# clock10.net
KiCad netlist of a schematic drawn in EAGLE
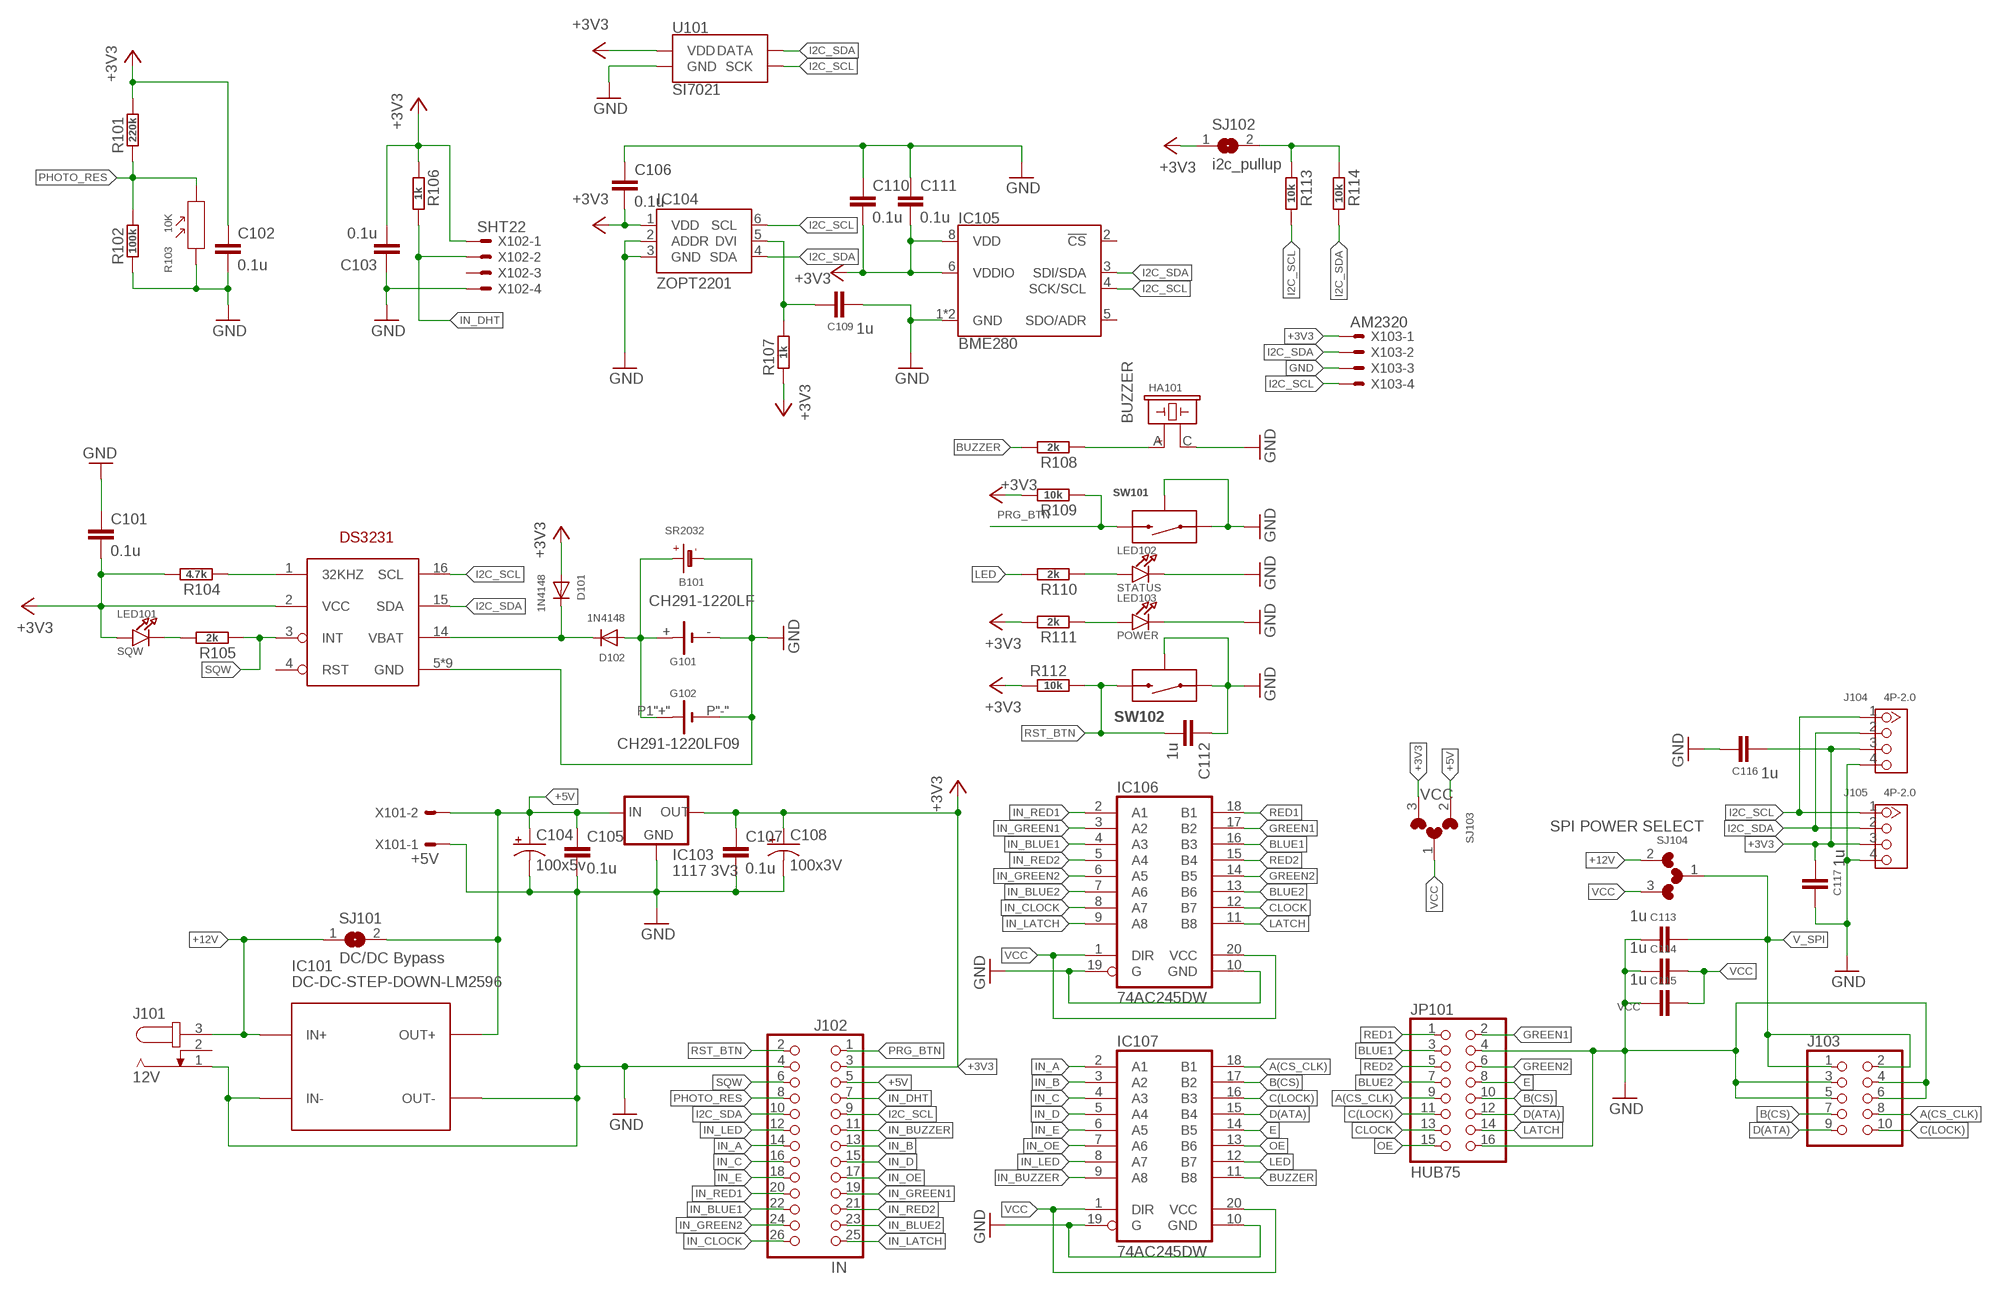
[diagram p0: schematic, sheet 1]
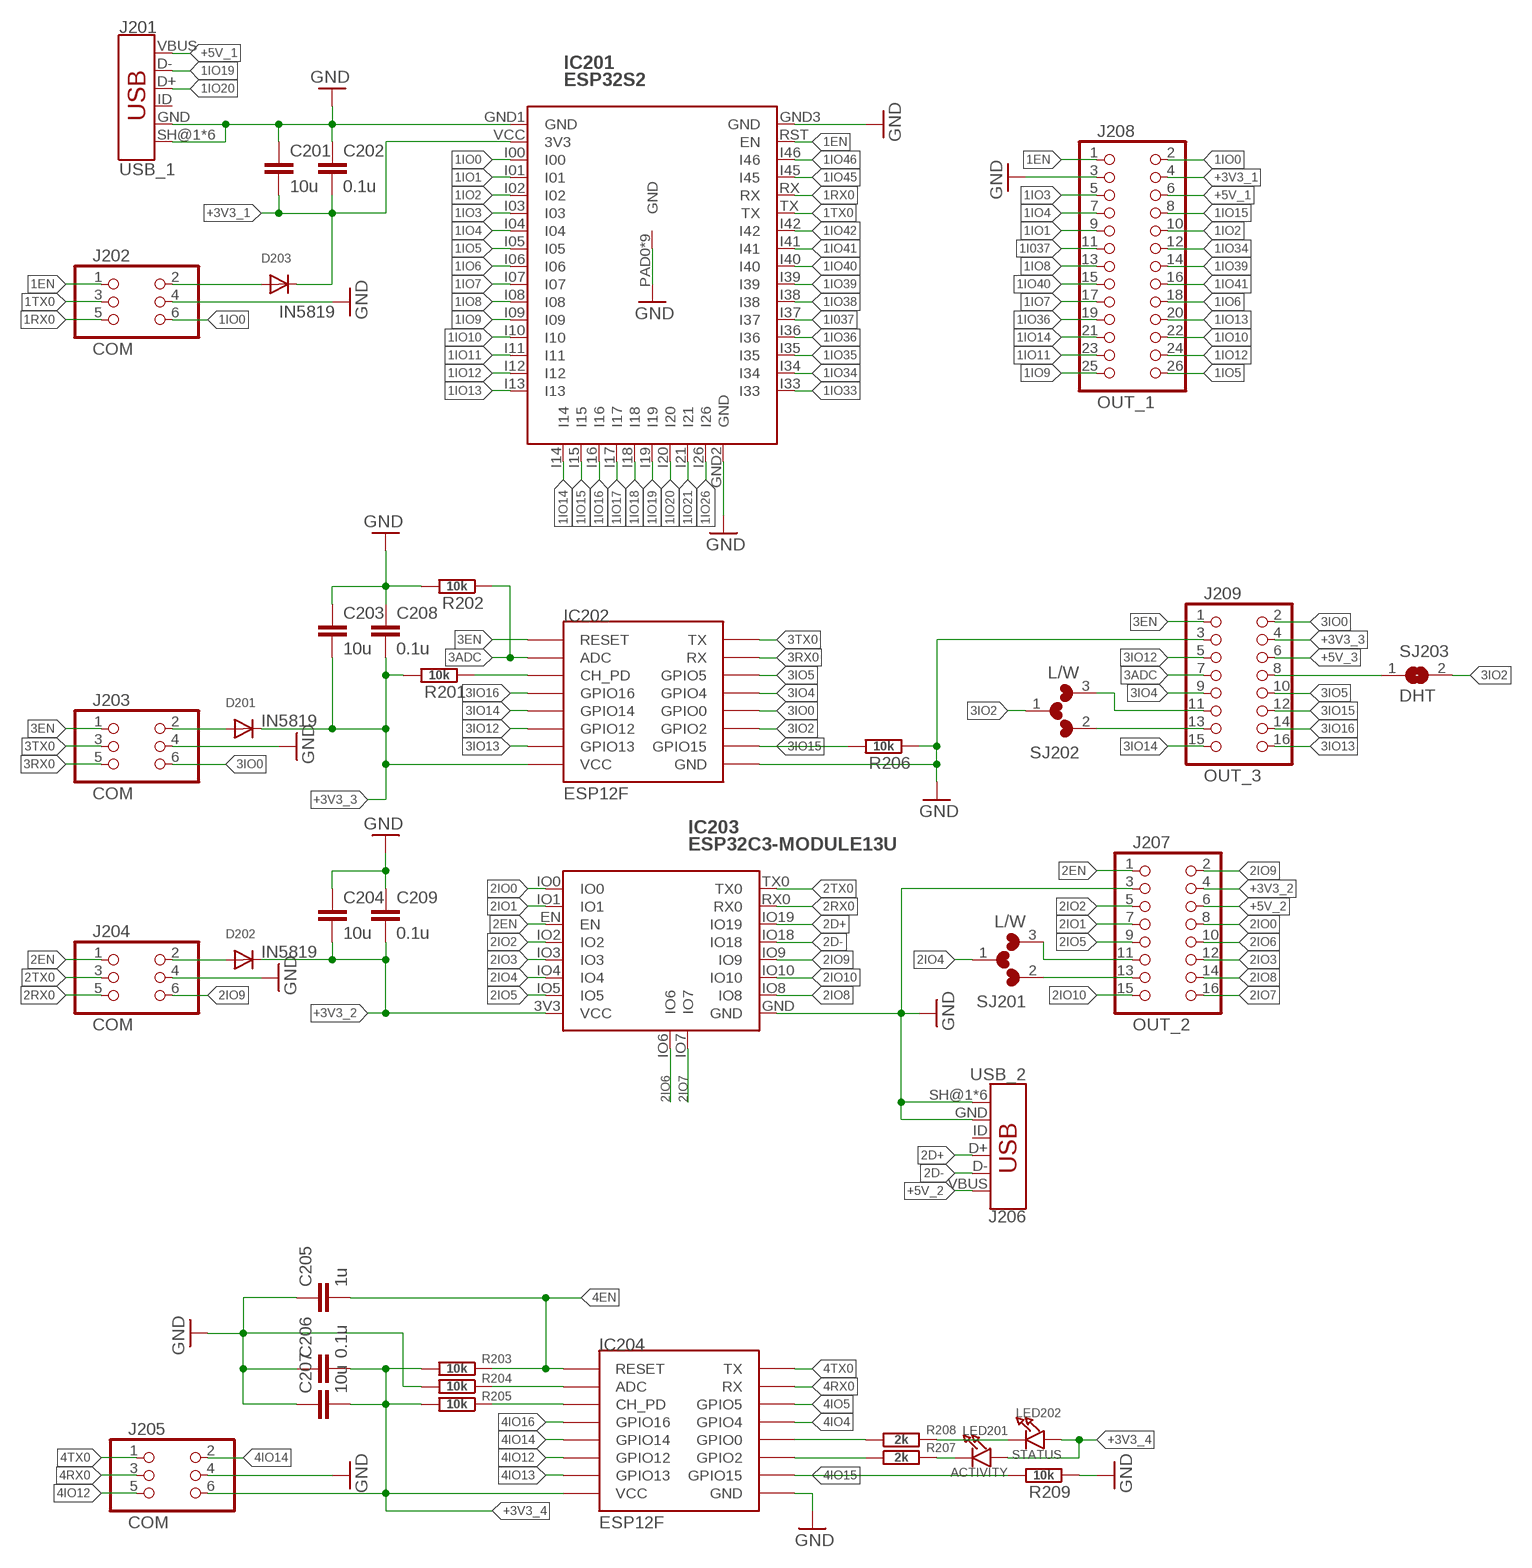
[diagram p1: schematic, sheet 2]
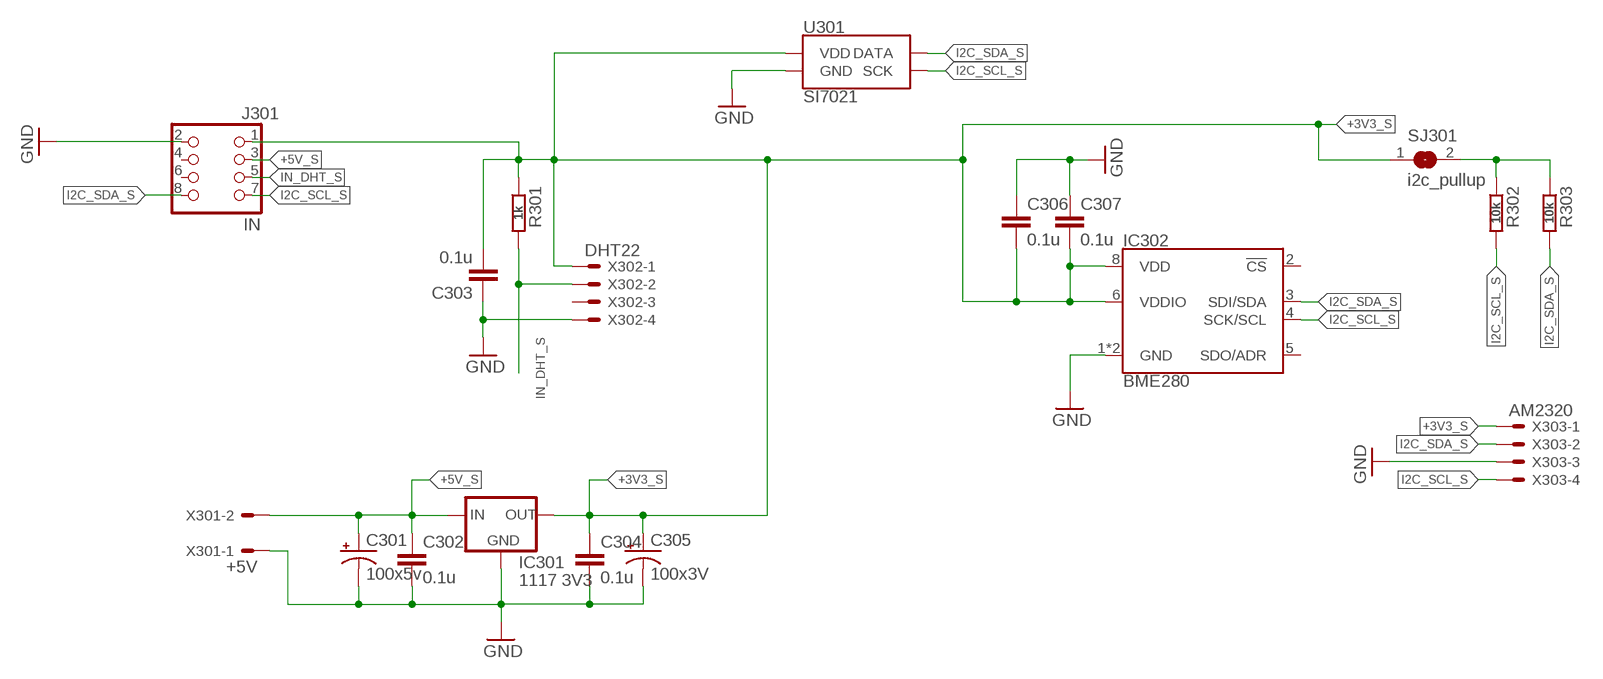
[diagram p2: schematic, sheet 3]

(export (version "E")
  (design (tool "Eeschema 10.0.6"))
  (components
    (comp (ref "C201")
      (value "10u")
      (footprint "eagle-import:0603-CAP")
      (libsource (lib "eagle-import") (part "CAP0603-CAP"))
    )
    (comp (ref "C202")
      (value "0.1u")
      (footprint "eagle-import:0603-CAP")
      (libsource (lib "eagle-import") (part "CAP0603-CAP"))
    )
    (comp (ref "C203")
      (value "10u")
      (footprint "eagle-import:0603-CAP")
      (libsource (lib "eagle-import") (part "CAP0603-CAP"))
    )
    (comp (ref "C204")
      (value "10u")
      (footprint "eagle-import:0603-CAP")
      (libsource (lib "eagle-import") (part "CAP0603-CAP"))
    )
    (comp (ref "C205")
      (value "1u")
      (footprint "eagle-import:0603-CAP")
      (libsource (lib "eagle-import") (part "CAP0603-CAP"))
    )
    (comp (ref "C206")
      (value "0.1u")
      (footprint "eagle-import:0603-CAP")
      (libsource (lib "eagle-import") (part "CAP0603-CAP"))
    )
    (comp (ref "C207")
      (value "10u")
      (footprint "eagle-import:0603-CAP")
      (libsource (lib "eagle-import") (part "CAP0603-CAP"))
    )
    (comp (ref "C208")
      (value "0.1u")
      (footprint "eagle-import:0603-CAP")
      (libsource (lib "eagle-import") (part "CAP0603-CAP"))
    )
    (comp (ref "C209")
      (value "0.1u")
      (footprint "eagle-import:0603-CAP")
      (libsource (lib "eagle-import") (part "CAP0603-CAP"))
    )
    (comp (ref "D201")
      (value "IN5819")
      (footprint "eagle-import:SOD123")
      (libsource (lib "eagle-import") (part "DIODE-SOD123"))
    )
    (comp (ref "D202")
      (value "IN5819")
      (footprint "eagle-import:SOD123")
      (libsource (lib "eagle-import") (part "DIODE-SOD123"))
    )
    (comp (ref "D203")
      (value "IN5819")
      (footprint "eagle-import:SOD123")
      (libsource (lib "eagle-import") (part "DIODE-SOD123"))
    )
    (comp (ref "IC201")
      (value "ESP32S2")
      (footprint "eagle-import:ESP-12K")
      (libsource (lib "eagle-import") (part "ESP32S2-MODULEAI"))
    )
    (comp (ref "IC202")
      (value "ESP12F")
      (footprint "eagle-import:ESP12-SMD")
      (libsource (lib "eagle-import") (part "ESP12SMD"))
    )
    (comp (ref "IC203")
      (value "ESP32C3-MODULE13U")
      (footprint "eagle-import:ESP32C3-13U")
      (libsource (lib "eagle-import") (part "ESP32C3-MODULE13U"))
    )
    (comp (ref "IC204")
      (value "ESP12F")
      (footprint "eagle-import:ESP12-SMD")
      (libsource (lib "eagle-import") (part "ESP12SMD"))
    )
    (comp (ref "J201")
      (value "USB_1")
      (footprint "eagle-import:USB-B-MICRO-SMD_MY")
      (libsource (lib "eagle-import") (part "USB_MICRO-BFEMALE_SMT_"))
    )
    (comp (ref "J202")
      (value "COM")
      (footprint "eagle-import:2X03_SMT")
      (libsource (lib "eagle-import") (part "HEADER-2X3SMT"))
    )
    (comp (ref "J203")
      (value "COM")
      (footprint "eagle-import:2X03_SMT")
      (libsource (lib "eagle-import") (part "HEADER-2X3SMT"))
    )
    (comp (ref "J204")
      (value "COM")
      (footprint "eagle-import:2X03_SMT")
      (libsource (lib "eagle-import") (part "HEADER-2X3SMT"))
    )
    (comp (ref "J205")
      (value "COM")
      (footprint "eagle-import:2X03_SMT")
      (libsource (lib "eagle-import") (part "HEADER-2X3SMT"))
    )
    (comp (ref "J206")
      (value "USB_2")
      (footprint "eagle-import:USB-B-MICRO-SMD_MY")
      (libsource (lib "eagle-import") (part "USB_MICRO-BFEMALE_SMT_"))
    )
    (comp (ref "J207")
      (value "OUT_2")
      (footprint "eagle-import:2X8")
      (libsource (lib "eagle-import") (part "HEADER-2X8"))
    )
    (comp (ref "J208")
      (value "OUT_1")
      (footprint "eagle-import:2X13")
      (libsource (lib "eagle-import") (part "HEADER-2X13"))
    )
    (comp (ref "J209")
      (value "OUT_3")
      (footprint "eagle-import:2X8")
      (libsource (lib "eagle-import") (part "HEADER-2X8"))
    )
    (comp (ref "LED201")
      (value "ACTIVITY")
      (footprint "eagle-import:CHIPLED_0603")
      (libsource (lib "eagle-import") (part "LED0603"))
    )
    (comp (ref "LED202")
      (value "STATUS")
      (footprint "eagle-import:CHIPLED_0603")
      (libsource (lib "eagle-import") (part "LED0603"))
    )
    (comp (ref "R201")
      (value "10k")
      (footprint "eagle-import:R0603")
      (libsource (lib "eagle-import") (part "R-EU_R0603"))
    )
    (comp (ref "R202")
      (value "10k")
      (footprint "eagle-import:R0603")
      (libsource (lib "eagle-import") (part "R-EU_R0603"))
    )
    (comp (ref "R203")
      (value "10k")
      (footprint "eagle-import:R0603")
      (libsource (lib "eagle-import") (part "R-EU_R0603"))
    )
    (comp (ref "R204")
      (value "10k")
      (footprint "eagle-import:R0603")
      (libsource (lib "eagle-import") (part "R-EU_R0603"))
    )
    (comp (ref "R205")
      (value "10k")
      (footprint "eagle-import:R0603")
      (libsource (lib "eagle-import") (part "R-EU_R0603"))
    )
    (comp (ref "R206")
      (value "10k")
      (footprint "eagle-import:R0603")
      (libsource (lib "eagle-import") (part "R-EU_R0603"))
    )
    (comp (ref "R207")
      (value "2k")
      (footprint "eagle-import:R0603")
      (libsource (lib "eagle-import") (part "R-EU_R0603"))
    )
    (comp (ref "R208")
      (value "2k")
      (footprint "eagle-import:R0603")
      (libsource (lib "eagle-import") (part "R-EU_R0603"))
    )
    (comp (ref "R209")
      (value "10k")
      (footprint "eagle-import:R0603")
      (libsource (lib "eagle-import") (part "R-EU_R0603"))
    )
    (comp (ref "SJ201")
      (value "L/W")
      (footprint "eagle-import:MICROBUILDER_SOLDERJUMPER_ARROW_NOPASTE_3")
      (libsource (lib "eagle-import") (part "MICROBUILDER_SOLDERJUMPER3"))
    )
    (comp (ref "SJ202")
      (value "L/W")
      (footprint "eagle-import:MICROBUILDER_SOLDERJUMPER_ARROW_NOPASTE_3")
      (libsource (lib "eagle-import") (part "MICROBUILDER_SOLDERJUMPER3"))
    )
    (comp (ref "SJ203")
      (value "DHT")
      (footprint "eagle-import:MICROBUILDER_SOLDERJUMPER_ARROW_NOPASTE")
      (libsource (lib "eagle-import") (part "MICROBUILDER_SOLDERJUMPER"))
    )
    (comp (ref "C301")
      (value "100x5v")
      (footprint "eagle-import:CPOL-RADIAL-100UF-25V")
      (libsource (lib "eagle-import") (part "CAP_POLPTH1"))
    )
    (comp (ref "C302")
      (value "0.1u")
      (footprint "eagle-import:0603-CAP")
      (libsource (lib "eagle-import") (part "CAP0603-CAP"))
    )
    (comp (ref "C303")
      (value "0.1u")
      (footprint "eagle-import:0603-CAP")
      (libsource (lib "eagle-import") (part "CAP0603-CAP"))
    )
    (comp (ref "C304")
      (value "0.1u")
      (footprint "eagle-import:0603-CAP")
      (libsource (lib "eagle-import") (part "CAP0603-CAP"))
    )
    (comp (ref "C305")
      (value "100x3V")
      (footprint "eagle-import:CPOL-RADIAL-100UF-25V")
      (libsource (lib "eagle-import") (part "CAP_POLPTH1"))
    )
    (comp (ref "C306")
      (value "0.1u")
      (footprint "eagle-import:0603-CAP")
      (libsource (lib "eagle-import") (part "CAP0603-CAP"))
    )
    (comp (ref "C307")
      (value "0.1u")
      (footprint "eagle-import:0603-CAP")
      (libsource (lib "eagle-import") (part "CAP0603-CAP"))
    )
    (comp (ref "IC301")
      (value "1117 3V3")
      (footprint "eagle-import:SOT223")
      (libsource (lib "eagle-import") (part "V_REG_LD1117VXXSMD"))
    )
    (comp (ref "IC302")
      (value "BME280")
      (footprint "eagle-import:LGA-8-2.5X2.5")
      (libsource (lib "eagle-import") (part "BME280"))
    )
    (comp (ref "J301")
      (value "IN")
      (footprint "eagle-import:2X04")
      (libsource (lib "eagle-import") (part "HEADER-2X4"))
    )
    (comp (ref "R301")
      (value "1k")
      (footprint "eagle-import:R0603")
      (libsource (lib "eagle-import") (part "R-EU_R0603"))
    )
    (comp (ref "R302")
      (value "10k")
      (footprint "eagle-import:R0603")
      (libsource (lib "eagle-import") (part "R-EU_R0603"))
    )
    (comp (ref "R303")
      (value "10k")
      (footprint "eagle-import:R0603")
      (libsource (lib "eagle-import") (part "R-EU_R0603"))
    )
    (comp (ref "SJ301")
      (value "i2c_pullup")
      (footprint "eagle-import:MICROBUILDER_SOLDERJUMPER_ARROW_NOPASTE")
      (libsource (lib "eagle-import") (part "MICROBUILDER_SOLDERJUMPER"))
    )
    (comp (ref "U301")
      (value "SI7021")
      (footprint "eagle-import:DFN-6-3X3-SI7021")
      (libsource (lib "eagle-import") (part "SI7021"))
    )
    (comp (ref "X301")
      (value "+5V")
      (footprint "eagle-import:70543-02")
      (libsource (lib "eagle-import") (part "C-GRID-02-70543"))
    )
    (comp (ref "X302")
      (value "DHT22")
      (footprint "eagle-import:70543-04")
      (libsource (lib "eagle-import") (part "C-GRID-04-70543"))
    )
    (comp (ref "X303")
      (value "AM2320")
      (footprint "eagle-import:70543-04")
      (libsource (lib "eagle-import") (part "C-GRID-04-70543"))
    )
    (comp (ref "B101")
      (value "SR2032")
      (footprint "eagle-import:CR2032")
      (libsource (lib "eagle-import") (part "BATTERYCR2032"))
    )
    (comp (ref "C101")
      (value "0.1u")
      (footprint "eagle-import:0603-CAP")
      (libsource (lib "eagle-import") (part "CAP0603-CAP"))
    )
    (comp (ref "C102")
      (value "0.1u")
      (footprint "eagle-import:0603-CAP")
      (libsource (lib "eagle-import") (part "CAP0603-CAP"))
    )
    (comp (ref "C103")
      (value "0.1u")
      (footprint "eagle-import:0603-CAP")
      (libsource (lib "eagle-import") (part "CAP0603-CAP"))
    )
    (comp (ref "C104")
      (value "100x5v")
      (footprint "eagle-import:CPOL-RADIAL-100UF-25V")
      (libsource (lib "eagle-import") (part "CAP_POLPTH1"))
    )
    (comp (ref "C105")
      (value "0.1u")
      (footprint "eagle-import:0603-CAP")
      (libsource (lib "eagle-import") (part "CAP0603-CAP"))
    )
    (comp (ref "C106")
      (value "0.1u")
      (footprint "eagle-import:0603-CAP")
      (libsource (lib "eagle-import") (part "CAP0603-CAP"))
    )
    (comp (ref "C107")
      (value "0.1u")
      (footprint "eagle-import:0603-CAP")
      (libsource (lib "eagle-import") (part "CAP0603-CAP"))
    )
    (comp (ref "C108")
      (value "100x3V")
      (footprint "eagle-import:CPOL-RADIAL-100UF-25V")
      (libsource (lib "eagle-import") (part "CAP_POLPTH1"))
    )
    (comp (ref "C109")
      (value "1u")
      (footprint "eagle-import:0603-CAP")
      (libsource (lib "eagle-import") (part "CAP0603-CAP"))
    )
    (comp (ref "C110")
      (value "0.1u")
      (footprint "eagle-import:0603-CAP")
      (libsource (lib "eagle-import") (part "CAP0603-CAP"))
    )
    (comp (ref "C111")
      (value "0.1u")
      (footprint "eagle-import:0603-CAP")
      (libsource (lib "eagle-import") (part "CAP0603-CAP"))
    )
    (comp (ref "C112")
      (value "1u")
      (footprint "eagle-import:0603-CAP")
      (libsource (lib "eagle-import") (part "CAP0603-CAP"))
    )
    (comp (ref "C113")
      (value "1u")
      (footprint "eagle-import:0603-CAP")
      (libsource (lib "eagle-import") (part "CAP0603-CAP"))
    )
    (comp (ref "C114")
      (value "1u")
      (footprint "eagle-import:0603-CAP")
      (libsource (lib "eagle-import") (part "CAP0603-CAP"))
    )
    (comp (ref "C115")
      (value "1u")
      (footprint "eagle-import:0603-CAP")
      (libsource (lib "eagle-import") (part "CAP0603-CAP"))
    )
    (comp (ref "C116")
      (value "1u")
      (footprint "eagle-import:0603-CAP")
      (libsource (lib "eagle-import") (part "CAP0603-CAP"))
    )
    (comp (ref "C117")
      (value "1u")
      (footprint "eagle-import:0603-CAP")
      (libsource (lib "eagle-import") (part "CAP0603-CAP"))
    )
    (comp (ref "D101")
      (value "1N4148")
      (footprint "eagle-import:SOD-323F")
      (libsource (lib "eagle-import") (part "DIODESOD-323F"))
    )
    (comp (ref "D102")
      (value "1N4148")
      (footprint "eagle-import:SOD-323F")
      (libsource (lib "eagle-import") (part "DIODESOD-323F"))
    )
    (comp (ref "G101")
      (value "CH291-1220LF")
      (footprint "eagle-import:CH291-1220LF")
      (libsource (lib "eagle-import") (part "CH291-1220LF"))
    )
    (comp (ref "G102")
      (value "CH291-1220LF09")
      (footprint "eagle-import:CH23-09LF")
      (libsource (lib "eagle-import") (part "CH291-1220LF09"))
    )
    (comp (ref "HA101")
      (value "BUZZER")
      (footprint "eagle-import:PBUZ_12X7.5")
      (libsource (lib "eagle-import") (part "PIEZO_BUZZERHYDZ12X7.5"))
    )
    (comp (ref "IC101")
      (value "DC-DC-STEP-DOWN-LM2596")
      (footprint "eagle-import:DC-DC-STEP-DOWN-LM2596")
      (libsource (lib "eagle-import") (part "DC-DC-STEP-DOWN-LM2596"))
    )
    (comp (ref "IC102")
      (value "DS3231W")
      (footprint "eagle-import:SO16W")
      (libsource (lib "eagle-import") (part "DS3231W"))
    )
    (comp (ref "IC103")
      (value "1117 3V3")
      (footprint "eagle-import:SOT223")
      (libsource (lib "eagle-import") (part "V_REG_LD1117VXXSMD"))
    )
    (comp (ref "IC104")
      (value "ZOPT2201")
      (footprint "eagle-import:WSOF6L")
      (libsource (lib "eagle-import") (part "BH1750"))
    )
    (comp (ref "IC105")
      (value "BME280")
      (footprint "eagle-import:LGA-8-2.5X2.5")
      (libsource (lib "eagle-import") (part "BME280"))
    )
    (comp (ref "IC106")
      (value "74AC245DW")
      (footprint "eagle-import:SO20W")
      (libsource (lib "eagle-import") (part "74245DWAC"))
    )
    (comp (ref "IC107")
      (value "74AC245DW")
      (footprint "eagle-import:SO20W")
      (libsource (lib "eagle-import") (part "74245DWAC"))
    )
    (comp (ref "J101")
      (value "12V")
      (footprint "eagle-import:SPC4077")
      (libsource (lib "eagle-import") (part "JACK-PLUG0"))
    )
    (comp (ref "J102")
      (value "IN")
      (footprint "eagle-import:2X13")
      (libsource (lib "eagle-import") (part "HEADER-2X13"))
    )
    (comp (ref "J103")
      (value "HEADER-2X5IDC")
      (footprint "eagle-import:2X05_IDC")
      (libsource (lib "eagle-import") (part "HEADER-2X5IDC"))
    )
    (comp (ref "J104")
      (value "4P-2.0")
      (footprint "eagle-import:HW4-2.0")
      (libsource (lib "eagle-import") (part "GROVE-CONNECTOR-DIP(4P-2.0)"))
    )
    (comp (ref "J105")
      (value "4P-2.0")
      (footprint "eagle-import:HW4-2.0")
      (libsource (lib "eagle-import") (part "GROVE-CONNECTOR-DIP(4P-2.0)"))
    )
    (comp (ref "JP101")
      (value "HUB75")
      (footprint "eagle-import:2X08")
      (libsource (lib "eagle-import") (part "PINHD-2X8"))
    )
    (comp (ref "LED101")
      (value "SQW")
      (footprint "eagle-import:CHIPLED_0603")
      (libsource (lib "eagle-import") (part "LED0603"))
    )
    (comp (ref "LED102")
      (value "STATUS")
      (footprint "eagle-import:CHIPLED_0603")
      (libsource (lib "eagle-import") (part "LED0603"))
    )
    (comp (ref "LED103")
      (value "POWER")
      (footprint "eagle-import:CHIPLED_0603")
      (libsource (lib "eagle-import") (part "LED0603"))
    )
    (comp (ref "R101")
      (value "220k")
      (footprint "eagle-import:R0603")
      (libsource (lib "eagle-import") (part "R-EU_R0603"))
    )
    (comp (ref "R102")
      (value "100k")
      (footprint "eagle-import:R0603")
      (libsource (lib "eagle-import") (part "R-EU_R0603"))
    )
    (comp (ref "R103")
      (value "10K")
      (footprint "eagle-import:SNR2-3.0")
      (fields (field (name "MPN") "PHOTORESISTOR-5528-10K"))
      (libsource (lib "eagle-import") (part "PHOTORESISTOR-5528-10K(2P-5.0X4.2MM)"))
    )
    (comp (ref "R104")
      (value "4.7k")
      (footprint "eagle-import:R0603")
      (libsource (lib "eagle-import") (part "R-EU_R0603"))
    )
    (comp (ref "R105")
      (value "2k")
      (footprint "eagle-import:R0603")
      (libsource (lib "eagle-import") (part "R-EU_R0603"))
    )
    (comp (ref "R106")
      (value "1k")
      (footprint "eagle-import:R0603")
      (libsource (lib "eagle-import") (part "R-EU_R0603"))
    )
    (comp (ref "R107")
      (value "1k")
      (footprint "eagle-import:R0603")
      (libsource (lib "eagle-import") (part "R-EU_R0603"))
    )
    (comp (ref "R108")
      (value "2k")
      (footprint "eagle-import:R0603")
      (libsource (lib "eagle-import") (part "R-EU_R0603"))
    )
    (comp (ref "R109")
      (value "10k")
      (footprint "eagle-import:R0603")
      (libsource (lib "eagle-import") (part "R-EU_R0603"))
    )
    (comp (ref "R110")
      (value "2k")
      (footprint "eagle-import:R0603")
      (libsource (lib "eagle-import") (part "R-EU_R0603"))
    )
    (comp (ref "R111")
      (value "2k")
      (footprint "eagle-import:R0603")
      (libsource (lib "eagle-import") (part "R-EU_R0603"))
    )
    (comp (ref "R112")
      (value "10k")
      (footprint "eagle-import:R0603")
      (libsource (lib "eagle-import") (part "R-EU_R0603"))
    )
    (comp (ref "R113")
      (value "10k")
      (footprint "eagle-import:R0603")
      (libsource (lib "eagle-import") (part "R-EU_R0603"))
    )
    (comp (ref "R114")
      (value "10k")
      (footprint "eagle-import:R0603")
      (libsource (lib "eagle-import") (part "R-EU_R0603"))
    )
    (comp (ref "SJ101")
      (value "DC/DC Bypass")
      (footprint "eagle-import:MICROBUILDER_SOLDERJUMPER_ARROW_NOPASTE")
      (libsource (lib "eagle-import") (part "MICROBUILDER_SOLDERJUMPER"))
    )
    (comp (ref "SJ102")
      (value "i2c_pullup")
      (footprint "eagle-import:MICROBUILDER_SOLDERJUMPER_ARROW_NOPASTE")
      (libsource (lib "eagle-import") (part "MICROBUILDER_SOLDERJUMPER"))
    )
    (comp (ref "SJ103")
      (value "VCC")
      (footprint "eagle-import:MICROBUILDER_SOLDERJUMPER_ARROW_NOPASTE_3")
      (libsource (lib "eagle-import") (part "MICROBUILDER_SOLDERJUMPER3"))
    )
    (comp (ref "SJ104")
      (value "SPI POWER SELECT")
      (footprint "eagle-import:MICROBUILDER_SOLDERJUMPER_ARROW_NOPASTE_3")
      (libsource (lib "eagle-import") (part "MICROBUILDER_SOLDERJUMPER3"))
    )
    (comp (ref "SW101")
      (value "PRG")
      (footprint "eagle-import:MICROPUSH-BUT_TOP")
      (libsource (lib "eagle-import") (part "MICROSWITCH-BUTTON"))
    )
    (comp (ref "SW102")
      (value "RST")
      (footprint "eagle-import:MICROPUSH-BUT_TOP")
      (libsource (lib "eagle-import") (part "MICROSWITCH-BUTTON"))
    )
    (comp (ref "U101")
      (value "SI7021")
      (footprint "eagle-import:DFN-6-3X3-SI7021")
      (libsource (lib "eagle-import") (part "SI7021"))
    )
    (comp (ref "X101")
      (value "+5V")
      (footprint "eagle-import:70543-02")
      (libsource (lib "eagle-import") (part "C-GRID-02-70543"))
    )
    (comp (ref "X102")
      (value "SHT22")
      (footprint "eagle-import:70543-04")
      (libsource (lib "eagle-import") (part "C-GRID-04-70543"))
    )
    (comp (ref "X103")
      (value "AM2320")
      (footprint "eagle-import:70543-04")
      (libsource (lib "eagle-import") (part "C-GRID-04-70543"))
    )
  )
  (nets
    (net (code "1") (name "+3V3") (class "Default")
      (node (ref "C101") (pin "2") (pinfunction "2_2") (pintype "passive"))
      (node (ref "C102") (pin "1") (pinfunction "1_1") (pintype "passive"))
      (node (ref "C103") (pin "2") (pinfunction "2_2") (pintype "passive"))
      (node (ref "C106") (pin "2") (pinfunction "2_2") (pintype "passive"))
      (node (ref "C107") (pin "1") (pinfunction "1_1") (pintype "passive"))
      (node (ref "C108") (pin "1") (pinfunction "+_1") (pintype "passive"))
      (node (ref "C110") (pin "2") (pinfunction "2_2") (pintype "passive"))
      (node (ref "C111") (pin "2") (pinfunction "2_2") (pintype "passive"))
      (node (ref "C116") (pin "2") (pinfunction "2_2") (pintype "passive"))
      (node (ref "C117") (pin "2") (pinfunction "2_2") (pintype "passive"))
      (node (ref "D101") (pin "A") (pinfunction "A_A") (pintype "passive"))
      (node (ref "IC102") (pin "2") (pinfunction "VCC_2") (pintype "input"))
      (node (ref "IC103") (pin "2") (pinfunction "OUT_2") (pintype "passive"))
      (node (ref "IC103") (pin "4") (pinfunction "OUT_4") (pintype "passive"))
      (node (ref "IC104") (pin "1") (pinfunction "VDD_1") (pintype "power_in"))
      (node (ref "IC105") (pin "6") (pinfunction "VDDIO_6") (pintype "bidirectional"))
      (node (ref "IC105") (pin "8") (pinfunction "VDD_8") (pintype "bidirectional"))
      (node (ref "J102") (pin "3") (pinfunction "3_3") (pintype "passive"))
      (node (ref "J104") (pin "3") (pinfunction "3_3") (pintype "bidirectional"))
      (node (ref "J105") (pin "3") (pinfunction "3_3") (pintype "bidirectional"))
      (node (ref "LED101") (pin "A") (pinfunction "A_A") (pintype "passive"))
      (node (ref "R101") (pin "2") (pinfunction "2_2") (pintype "passive"))
      (node (ref "R104") (pin "2") (pinfunction "2_2") (pintype "passive"))
      (node (ref "R106") (pin "1") (pinfunction "1_1") (pintype "passive"))
      (node (ref "R107") (pin "1") (pinfunction "1_1") (pintype "passive"))
      (node (ref "R109") (pin "2") (pinfunction "2_2") (pintype "passive"))
      (node (ref "R111") (pin "2") (pinfunction "2_2") (pintype "passive"))
      (node (ref "R112") (pin "1") (pinfunction "1_1") (pintype "passive"))
      (node (ref "SJ102") (pin "1") (pinfunction "1_1") (pintype "passive"))
      (node (ref "SJ103") (pin "3") (pinfunction "3_3") (pintype "passive"))
      (node (ref "U101") (pin "VDD") (pinfunction "VDD_VDD") (pintype "power_in"))
      (node (ref "X102") (pin "1") (pinfunction "S_1") (pintype "passive"))
      (node (ref "X103") (pin "1") (pinfunction "S_1") (pintype "passive"))
    )
    (net (code "2") (name "+3V3_1") (class "Default")
      (node (ref "C201") (pin "2") (pinfunction "2_2") (pintype "passive"))
      (node (ref "C202") (pin "2") (pinfunction "2_2") (pintype "passive"))
      (node (ref "D203") (pin "C") (pinfunction "C_C") (pintype "passive"))
      (node (ref "IC201") (pin "VCC") (pinfunction "3V3_VCC") (pintype "power_in"))
      (node (ref "J208") (pin "4") (pinfunction "4_4") (pintype "passive"))
    )
    (net (code "3") (name "+3V3_2") (class "Default")
      (node (ref "C204") (pin "2") (pinfunction "2_2") (pintype "passive"))
      (node (ref "C209") (pin "2") (pinfunction "2_2") (pintype "passive"))
      (node (ref "D202") (pin "C") (pinfunction "C_C") (pintype "passive"))
      (node (ref "IC203") (pin "3V3") (pinfunction "VCC_3V3") (pintype "power_in"))
      (node (ref "J207") (pin "4") (pinfunction "4_4") (pintype "passive"))
    )
    (net (code "4") (name "+3V3_3") (class "Default")
      (node (ref "C203") (pin "2") (pinfunction "2_2") (pintype "passive"))
      (node (ref "C208") (pin "2") (pinfunction "2_2") (pintype "passive"))
      (node (ref "D201") (pin "C") (pinfunction "C_C") (pintype "passive"))
      (node (ref "IC202") (pin "VCC") (pinfunction "VCC_VCC") (pintype "bidirectional"))
      (node (ref "J209") (pin "4") (pinfunction "4_4") (pintype "passive"))
      (node (ref "R201") (pin "2") (pinfunction "2_2") (pintype "passive"))
    )
    (net (code "5") (name "+3V3_4") (class "Default")
      (node (ref "C206") (pin "2") (pinfunction "2_2") (pintype "passive"))
      (node (ref "C207") (pin "2") (pinfunction "2_2") (pintype "passive"))
      (node (ref "IC204") (pin "VCC") (pinfunction "VCC_VCC") (pintype "bidirectional"))
      (node (ref "J205") (pin "6") (pinfunction "6_6") (pintype "passive"))
      (node (ref "LED201") (pin "A") (pinfunction "A_A") (pintype "passive"))
      (node (ref "LED202") (pin "A") (pinfunction "A_A") (pintype "passive"))
      (node (ref "R203") (pin "2") (pinfunction "2_2") (pintype "passive"))
      (node (ref "R205") (pin "2") (pinfunction "2_2") (pintype "passive"))
    )
    (net (code "6") (name "+3V3_S") (class "Default")
      (node (ref "C303") (pin "2") (pinfunction "2_2") (pintype "passive"))
      (node (ref "C304") (pin "1") (pinfunction "1_1") (pintype "passive"))
      (node (ref "C305") (pin "1") (pinfunction "+_1") (pintype "passive"))
      (node (ref "C306") (pin "2") (pinfunction "2_2") (pintype "passive"))
      (node (ref "C307") (pin "2") (pinfunction "2_2") (pintype "passive"))
      (node (ref "IC301") (pin "2") (pinfunction "OUT_2") (pintype "passive"))
      (node (ref "IC301") (pin "4") (pinfunction "OUT_4") (pintype "passive"))
      (node (ref "IC302") (pin "6") (pinfunction "VDDIO_6") (pintype "bidirectional"))
      (node (ref "IC302") (pin "8") (pinfunction "VDD_8") (pintype "bidirectional"))
      (node (ref "J301") (pin "1") (pinfunction "1_1") (pintype "passive"))
      (node (ref "R301") (pin "1") (pinfunction "1_1") (pintype "passive"))
      (node (ref "SJ301") (pin "1") (pinfunction "1_1") (pintype "passive"))
      (node (ref "U301") (pin "VDD") (pinfunction "VDD_VDD") (pintype "power_in"))
      (node (ref "X302") (pin "1") (pinfunction "S_1") (pintype "passive"))
      (node (ref "X303") (pin "1") (pinfunction "S_1") (pintype "passive"))
    )
    (net (code "7") (name "+5V") (class "Default")
      (node (ref "C104") (pin "1") (pinfunction "+_1") (pintype "passive"))
      (node (ref "C105") (pin "1") (pinfunction "1_1") (pintype "passive"))
      (node (ref "IC101") (pin "OUT+") (pinfunction "OUT+_OUT+") (pintype "bidirectional"))
      (node (ref "IC103") (pin "3") (pinfunction "IN_3") (pintype "input"))
      (node (ref "J102") (pin "5") (pinfunction "5_5") (pintype "passive"))
      (node (ref "SJ101") (pin "2") (pinfunction "2_2") (pintype "passive"))
      (node (ref "SJ103") (pin "2") (pinfunction "2_2") (pintype "passive"))
      (node (ref "X101") (pin "2") (pinfunction "S_2") (pintype "passive"))
    )
    (net (code "8") (name "+5V_1") (class "Default")
      (node (ref "J201") (pin "VBUS") (pinfunction "VBUS_VBUS") (pintype "power_in"))
      (node (ref "J208") (pin "6") (pinfunction "6_6") (pintype "passive"))
    )
    (net (code "9") (name "+5V_2") (class "Default")
      (node (ref "J206") (pin "VBUS") (pinfunction "VBUS_VBUS") (pintype "power_in"))
      (node (ref "J207") (pin "6") (pinfunction "6_6") (pintype "passive"))
    )
    (net (code "10") (name "+5V_3") (class "Default")
      (node (ref "J209") (pin "6") (pinfunction "6_6") (pintype "passive"))
    )
    (net (code "11") (name "+5V_S") (class "Default")
      (node (ref "C301") (pin "1") (pinfunction "+_1") (pintype "passive"))
      (node (ref "C302") (pin "1") (pinfunction "1_1") (pintype "passive"))
      (node (ref "IC301") (pin "3") (pinfunction "IN_3") (pintype "input"))
      (node (ref "J301") (pin "3") (pinfunction "3_3") (pintype "passive"))
      (node (ref "X301") (pin "2") (pinfunction "S_2") (pintype "passive"))
    )
    (net (code "12") (name "+12V") (class "Default")
      (node (ref "IC101") (pin "IN+") (pinfunction "IN+_IN+") (pintype "bidirectional"))
      (node (ref "J101") (pin "3") (pinfunction "3_3") (pintype "passive"))
      (node (ref "SJ101") (pin "1") (pinfunction "1_1") (pintype "passive"))
      (node (ref "SJ104") (pin "2") (pinfunction "2_2") (pintype "passive"))
    )
    (net (code "13") (name "1EN") (class "Default")
      (node (ref "IC201") (pin "RST") (pinfunction "EN_RST") (pintype "input"))
      (node (ref "J202") (pin "1") (pinfunction "1_1") (pintype "passive"))
      (node (ref "J208") (pin "1") (pinfunction "1_1") (pintype "passive"))
    )
    (net (code "14") (name "1I037") (class "Default")
      (node (ref "IC201") (pin "I37") (pinfunction "I37_I37") (pintype "bidirectional"))
      (node (ref "J208") (pin "11") (pinfunction "11_11") (pintype "passive"))
    )
    (net (code "15") (name "1IO0") (class "Default")
      (node (ref "IC201") (pin "I00") (pinfunction "I00_I00") (pintype "bidirectional"))
      (node (ref "J202") (pin "6") (pinfunction "6_6") (pintype "passive"))
      (node (ref "J208") (pin "2") (pinfunction "2_2") (pintype "passive"))
    )
    (net (code "16") (name "1IO1") (class "Default")
      (node (ref "IC201") (pin "I01") (pinfunction "I01_I01") (pintype "bidirectional"))
      (node (ref "J208") (pin "9") (pinfunction "9_9") (pintype "passive"))
    )
    (net (code "17") (name "1IO2") (class "Default")
      (node (ref "IC201") (pin "I02") (pinfunction "I02_I02") (pintype "bidirectional"))
      (node (ref "J208") (pin "10") (pinfunction "10_10") (pintype "passive"))
    )
    (net (code "18") (name "1IO3") (class "Default")
      (node (ref "IC201") (pin "I03") (pinfunction "I03_I03") (pintype "bidirectional"))
      (node (ref "J208") (pin "5") (pinfunction "5_5") (pintype "passive"))
    )
    (net (code "19") (name "1IO4") (class "Default")
      (node (ref "IC201") (pin "I04") (pinfunction "I04_I04") (pintype "bidirectional"))
      (node (ref "J208") (pin "7") (pinfunction "7_7") (pintype "passive"))
    )
    (net (code "20") (name "1IO5") (class "Default")
      (node (ref "IC201") (pin "I05") (pinfunction "I05_I05") (pintype "bidirectional"))
      (node (ref "J208") (pin "26") (pinfunction "26_26") (pintype "passive"))
    )
    (net (code "21") (name "1IO6") (class "Default")
      (node (ref "IC201") (pin "I06") (pinfunction "I06_I06") (pintype "bidirectional"))
      (node (ref "J208") (pin "18") (pinfunction "18_18") (pintype "passive"))
    )
    (net (code "22") (name "1IO7") (class "Default")
      (node (ref "IC201") (pin "I07") (pinfunction "I07_I07") (pintype "bidirectional"))
      (node (ref "J208") (pin "17") (pinfunction "17_17") (pintype "passive"))
    )
    (net (code "23") (name "1IO8") (class "Default")
      (node (ref "IC201") (pin "I08") (pinfunction "I08_I08") (pintype "bidirectional"))
      (node (ref "J208") (pin "13") (pinfunction "13_13") (pintype "passive"))
    )
    (net (code "24") (name "1IO9") (class "Default")
      (node (ref "IC201") (pin "I09") (pinfunction "I09_I09") (pintype "bidirectional"))
      (node (ref "J208") (pin "25") (pinfunction "25_25") (pintype "passive"))
    )
    (net (code "25") (name "1IO10") (class "Default")
      (node (ref "IC201") (pin "I10") (pinfunction "I10_I10") (pintype "bidirectional"))
      (node (ref "J208") (pin "22") (pinfunction "22_22") (pintype "passive"))
    )
    (net (code "26") (name "1IO11") (class "Default")
      (node (ref "IC201") (pin "I11") (pinfunction "I11_I11") (pintype "bidirectional"))
      (node (ref "J208") (pin "23") (pinfunction "23_23") (pintype "passive"))
    )
    (net (code "27") (name "1IO12") (class "Default")
      (node (ref "IC201") (pin "I12") (pinfunction "I12_I12") (pintype "bidirectional"))
      (node (ref "J208") (pin "24") (pinfunction "24_24") (pintype "passive"))
    )
    (net (code "28") (name "1IO13") (class "Default")
      (node (ref "IC201") (pin "I13") (pinfunction "I13_I13") (pintype "bidirectional"))
      (node (ref "J208") (pin "20") (pinfunction "20_20") (pintype "passive"))
    )
    (net (code "29") (name "1IO14") (class "Default")
      (node (ref "IC201") (pin "I14") (pinfunction "I14_I14") (pintype "bidirectional"))
      (node (ref "J208") (pin "21") (pinfunction "21_21") (pintype "passive"))
    )
    (net (code "30") (name "1IO15") (class "Default")
      (node (ref "IC201") (pin "I15") (pinfunction "I15_I15") (pintype "bidirectional"))
      (node (ref "J208") (pin "8") (pinfunction "8_8") (pintype "passive"))
    )
    (net (code "31") (name "1IO16") (class "Default")
      (node (ref "IC201") (pin "I16") (pinfunction "I16_I16") (pintype "bidirectional"))
    )
    (net (code "32") (name "1IO17") (class "Default")
      (node (ref "IC201") (pin "I17") (pinfunction "I17_I17") (pintype "bidirectional"))
    )
    (net (code "33") (name "1IO18") (class "Default")
      (node (ref "IC201") (pin "I18") (pinfunction "I18_I18") (pintype "bidirectional"))
    )
    (net (code "34") (name "1IO19") (class "Default")
      (node (ref "IC201") (pin "I19") (pinfunction "I19_I19") (pintype "bidirectional"))
      (node (ref "J201") (pin "D-") (pinfunction "D-_D-") (pintype "bidirectional"))
    )
    (net (code "35") (name "1IO20") (class "Default")
      (node (ref "IC201") (pin "I20") (pinfunction "I20_I20") (pintype "bidirectional"))
      (node (ref "J201") (pin "D+") (pinfunction "D+_D+") (pintype "bidirectional"))
    )
    (net (code "36") (name "1IO21") (class "Default")
      (node (ref "IC201") (pin "I21") (pinfunction "I21_I21") (pintype "bidirectional"))
    )
    (net (code "37") (name "1IO26") (class "Default")
      (node (ref "IC201") (pin "I26") (pinfunction "I26_I26") (pintype "bidirectional"))
    )
    (net (code "38") (name "1IO33") (class "Default")
      (node (ref "IC201") (pin "I33") (pinfunction "I33_I33") (pintype "bidirectional"))
    )
    (net (code "39") (name "1IO34") (class "Default")
      (node (ref "IC201") (pin "I34") (pinfunction "I34_I34") (pintype "bidirectional"))
      (node (ref "J208") (pin "12") (pinfunction "12_12") (pintype "passive"))
    )
    (net (code "40") (name "1IO35") (class "Default")
      (node (ref "IC201") (pin "I35") (pinfunction "I35_I35") (pintype "bidirectional"))
    )
    (net (code "41") (name "1IO36") (class "Default")
      (node (ref "IC201") (pin "I36") (pinfunction "I36_I36") (pintype "bidirectional"))
      (node (ref "J208") (pin "19") (pinfunction "19_19") (pintype "passive"))
    )
    (net (code "42") (name "1IO38") (class "Default")
      (node (ref "IC201") (pin "I38") (pinfunction "I38_I38") (pintype "bidirectional"))
    )
    (net (code "43") (name "1IO39") (class "Default")
      (node (ref "IC201") (pin "I39") (pinfunction "I39_I39") (pintype "bidirectional"))
      (node (ref "J208") (pin "14") (pinfunction "14_14") (pintype "passive"))
    )
    (net (code "44") (name "1IO40") (class "Default")
      (node (ref "IC201") (pin "I40") (pinfunction "I40_I40") (pintype "bidirectional"))
      (node (ref "J208") (pin "15") (pinfunction "15_15") (pintype "passive"))
    )
    (net (code "45") (name "1IO41") (class "Default")
      (node (ref "IC201") (pin "I41") (pinfunction "I41_I41") (pintype "bidirectional"))
      (node (ref "J208") (pin "16") (pinfunction "16_16") (pintype "passive"))
    )
    (net (code "46") (name "1IO42") (class "Default")
      (node (ref "IC201") (pin "I42") (pinfunction "I42_I42") (pintype "bidirectional"))
    )
    (net (code "47") (name "1IO45") (class "Default")
      (node (ref "IC201") (pin "I45") (pinfunction "I45_I45") (pintype "output"))
    )
    (net (code "48") (name "1IO46") (class "Default")
      (node (ref "IC201") (pin "I46") (pinfunction "I46_I46") (pintype "bidirectional"))
    )
    (net (code "49") (name "1RX0") (class "Default")
      (node (ref "IC201") (pin "RX") (pinfunction "RX_RX") (pintype "input"))
      (node (ref "J202") (pin "5") (pinfunction "5_5") (pintype "passive"))
    )
    (net (code "50") (name "1TX0") (class "Default")
      (node (ref "IC201") (pin "TX") (pinfunction "TX_TX") (pintype "output"))
      (node (ref "J202") (pin "3") (pinfunction "3_3") (pintype "passive"))
    )
    (net (code "51") (name "2D+") (class "Default")
      (node (ref "IC203") (pin "IO19") (pinfunction "IO19_IO19") (pintype "bidirectional"))
      (node (ref "J206") (pin "D+") (pinfunction "D+_D+") (pintype "bidirectional"))
    )
    (net (code "52") (name "2D-") (class "Default")
      (node (ref "IC203") (pin "IO18") (pinfunction "IO18_IO18") (pintype "bidirectional"))
      (node (ref "J206") (pin "D-") (pinfunction "D-_D-") (pintype "bidirectional"))
    )
    (net (code "53") (name "2EN") (class "Default")
      (node (ref "IC203") (pin "EN") (pinfunction "EN_EN") (pintype "bidirectional"))
      (node (ref "J204") (pin "1") (pinfunction "1_1") (pintype "passive"))
      (node (ref "J207") (pin "1") (pinfunction "1_1") (pintype "passive"))
    )
    (net (code "54") (name "2IO0") (class "Default")
      (node (ref "IC203") (pin "IO0") (pinfunction "IO0_IO0") (pintype "bidirectional"))
      (node (ref "J207") (pin "8") (pinfunction "8_8") (pintype "passive"))
    )
    (net (code "55") (name "2IO1") (class "Default")
      (node (ref "IC203") (pin "IO1") (pinfunction "IO1_IO1") (pintype "bidirectional"))
      (node (ref "J207") (pin "7") (pinfunction "7_7") (pintype "passive"))
    )
    (net (code "56") (name "2IO2") (class "Default")
      (node (ref "IC203") (pin "IO2") (pinfunction "IO2_IO2") (pintype "bidirectional"))
      (node (ref "J207") (pin "5") (pinfunction "5_5") (pintype "passive"))
    )
    (net (code "57") (name "2IO3") (class "Default")
      (node (ref "IC203") (pin "IO3") (pinfunction "IO3_IO3") (pintype "bidirectional"))
      (node (ref "J207") (pin "12") (pinfunction "12_12") (pintype "passive"))
    )
    (net (code "58") (name "2IO4") (class "Default")
      (node (ref "IC203") (pin "IO4") (pinfunction "IO4_IO4") (pintype "bidirectional"))
      (node (ref "SJ201") (pin "1") (pinfunction "1_1") (pintype "passive"))
    )
    (net (code "59") (name "2IO5") (class "Default")
      (node (ref "IC203") (pin "IO5") (pinfunction "IO5_IO5") (pintype "bidirectional"))
      (node (ref "J207") (pin "9") (pinfunction "9_9") (pintype "passive"))
    )
    (net (code "60") (name "2IO6") (class "Default")
      (node (ref "IC203") (pin "IO6") (pinfunction "IO6_IO6") (pintype "bidirectional"))
      (node (ref "J207") (pin "10") (pinfunction "10_10") (pintype "passive"))
    )
    (net (code "61") (name "2IO7") (class "Default")
      (node (ref "IC203") (pin "IO7") (pinfunction "IO7_IO7") (pintype "bidirectional"))
      (node (ref "J207") (pin "16") (pinfunction "16_16") (pintype "passive"))
    )
    (net (code "62") (name "2IO8") (class "Default")
      (node (ref "IC203") (pin "IO8") (pinfunction "IO8_IO8") (pintype "bidirectional"))
      (node (ref "J207") (pin "14") (pinfunction "14_14") (pintype "passive"))
    )
    (net (code "63") (name "2IO9") (class "Default")
      (node (ref "IC203") (pin "IO9") (pinfunction "IO9_IO9") (pintype "bidirectional"))
      (node (ref "J204") (pin "6") (pinfunction "6_6") (pintype "passive"))
      (node (ref "J207") (pin "2") (pinfunction "2_2") (pintype "passive"))
    )
    (net (code "64") (name "2IO10") (class "Default")
      (node (ref "IC203") (pin "IO10") (pinfunction "IO10_IO10") (pintype "bidirectional"))
      (node (ref "J207") (pin "15") (pinfunction "15_15") (pintype "passive"))
    )
    (net (code "65") (name "2RX0") (class "Default")
      (node (ref "IC203") (pin "RX0") (pinfunction "RX0_RX0") (pintype "input"))
      (node (ref "J204") (pin "5") (pinfunction "5_5") (pintype "passive"))
    )
    (net (code "66") (name "2TX0") (class "Default")
      (node (ref "IC203") (pin "TX0") (pinfunction "TX0_TX0") (pintype "output"))
      (node (ref "J204") (pin "3") (pinfunction "3_3") (pintype "passive"))
    )
    (net (code "67") (name "3ADC") (class "Default")
      (node (ref "IC202") (pin "ADC") (pinfunction "ADC_ADC") (pintype "bidirectional"))
      (node (ref "J209") (pin "7") (pinfunction "7_7") (pintype "passive"))
      (node (ref "R202") (pin "1") (pinfunction "1_1") (pintype "passive"))
    )
    (net (code "68") (name "3EN") (class "Default")
      (node (ref "IC202") (pin "RESET") (pinfunction "RESET_RESET") (pintype "bidirectional"))
      (node (ref "J203") (pin "1") (pinfunction "1_1") (pintype "passive"))
      (node (ref "J209") (pin "1") (pinfunction "1_1") (pintype "passive"))
    )
    (net (code "69") (name "3IO0") (class "Default")
      (node (ref "IC202") (pin "GPIO0") (pinfunction "GPIO0_GPIO0") (pintype "bidirectional"))
      (node (ref "J203") (pin "6") (pinfunction "6_6") (pintype "passive"))
      (node (ref "J209") (pin "2") (pinfunction "2_2") (pintype "passive"))
    )
    (net (code "70") (name "3IO2") (class "Default")
      (node (ref "IC202") (pin "GPIO2") (pinfunction "GPIO2_GPIO2") (pintype "bidirectional"))
      (node (ref "SJ202") (pin "1") (pinfunction "1_1") (pintype "passive"))
      (node (ref "SJ203") (pin "2") (pinfunction "2_2") (pintype "passive"))
    )
    (net (code "71") (name "3IO4") (class "Default")
      (node (ref "IC202") (pin "GPIO4") (pinfunction "GPIO4_GPIO4") (pintype "bidirectional"))
      (node (ref "J209") (pin "9") (pinfunction "9_9") (pintype "passive"))
    )
    (net (code "72") (name "3IO5") (class "Default")
      (node (ref "IC202") (pin "GPIO5") (pinfunction "GPIO5_GPIO5") (pintype "bidirectional"))
      (node (ref "J209") (pin "10") (pinfunction "10_10") (pintype "passive"))
    )
    (net (code "73") (name "3IO12") (class "Default")
      (node (ref "IC202") (pin "GPIO12") (pinfunction "GPIO12_GPIO12") (pintype "bidirectional"))
      (node (ref "J209") (pin "5") (pinfunction "5_5") (pintype "passive"))
    )
    (net (code "74") (name "3IO13") (class "Default")
      (node (ref "IC202") (pin "GPIO13") (pinfunction "GPIO13_GPIO13") (pintype "bidirectional"))
      (node (ref "J209") (pin "16") (pinfunction "16_16") (pintype "passive"))
    )
    (net (code "75") (name "3IO14") (class "Default")
      (node (ref "IC202") (pin "GPIO14") (pinfunction "GPIO14_GPIO14") (pintype "bidirectional"))
      (node (ref "J209") (pin "15") (pinfunction "15_15") (pintype "passive"))
    )
    (net (code "76") (name "3IO15") (class "Default")
      (node (ref "IC202") (pin "GPIO15") (pinfunction "GPIO15_GPIO15") (pintype "bidirectional"))
      (node (ref "J209") (pin "12") (pinfunction "12_12") (pintype "passive"))
      (node (ref "R206") (pin "2") (pinfunction "2_2") (pintype "passive"))
    )
    (net (code "77") (name "3IO16") (class "Default")
      (node (ref "IC202") (pin "GPIO16") (pinfunction "GPIO16_GPIO16") (pintype "bidirectional"))
      (node (ref "J209") (pin "14") (pinfunction "14_14") (pintype "passive"))
    )
    (net (code "78") (name "3RX0") (class "Default")
      (node (ref "IC202") (pin "RXD0") (pinfunction "RX_RXD0") (pintype "bidirectional"))
      (node (ref "J203") (pin "5") (pinfunction "5_5") (pintype "passive"))
    )
    (net (code "79") (name "3TX0") (class "Default")
      (node (ref "IC202") (pin "TXD0") (pinfunction "TX_TXD0") (pintype "bidirectional"))
      (node (ref "J203") (pin "3") (pinfunction "3_3") (pintype "passive"))
    )
    (net (code "80") (name "4EN") (class "Default")
      (node (ref "C205") (pin "2") (pinfunction "2_2") (pintype "passive"))
      (node (ref "IC204") (pin "RESET") (pinfunction "RESET_RESET") (pintype "bidirectional"))
      (node (ref "R203") (pin "1") (pinfunction "1_1") (pintype "passive"))
    )
    (net (code "81") (name "4IO4") (class "Default")
      (node (ref "IC204") (pin "GPIO4") (pinfunction "GPIO4_GPIO4") (pintype "bidirectional"))
    )
    (net (code "82") (name "4IO5") (class "Default")
      (node (ref "IC204") (pin "GPIO5") (pinfunction "GPIO5_GPIO5") (pintype "bidirectional"))
    )
    (net (code "83") (name "4IO12") (class "Default")
      (node (ref "IC204") (pin "GPIO12") (pinfunction "GPIO12_GPIO12") (pintype "bidirectional"))
      (node (ref "J205") (pin "5") (pinfunction "5_5") (pintype "passive"))
    )
    (net (code "84") (name "4IO13") (class "Default")
      (node (ref "IC204") (pin "GPIO13") (pinfunction "GPIO13_GPIO13") (pintype "bidirectional"))
    )
    (net (code "85") (name "4IO14") (class "Default")
      (node (ref "IC204") (pin "GPIO14") (pinfunction "GPIO14_GPIO14") (pintype "bidirectional"))
      (node (ref "J205") (pin "2") (pinfunction "2_2") (pintype "passive"))
    )
    (net (code "86") (name "4IO15") (class "Default")
      (node (ref "IC204") (pin "GPIO15") (pinfunction "GPIO15_GPIO15") (pintype "bidirectional"))
      (node (ref "R209") (pin "2") (pinfunction "2_2") (pintype "passive"))
    )
    (net (code "87") (name "4IO16") (class "Default")
      (node (ref "IC204") (pin "GPIO16") (pinfunction "GPIO16_GPIO16") (pintype "bidirectional"))
    )
    (net (code "88") (name "4RX0") (class "Default")
      (node (ref "IC204") (pin "RXD0") (pinfunction "RX_RXD0") (pintype "bidirectional"))
      (node (ref "J205") (pin "3") (pinfunction "3_3") (pintype "passive"))
    )
    (net (code "89") (name "4TX0") (class "Default")
      (node (ref "IC204") (pin "TXD0") (pinfunction "TX_TXD0") (pintype "bidirectional"))
      (node (ref "J205") (pin "1") (pinfunction "1_1") (pintype "passive"))
    )
    (net (code "90") (name "A(CS_CLK)") (class "Default")
      (node (ref "IC107") (pin "18") (pinfunction "B1_18") (pintype "bidirectional"))
      (node (ref "J103") (pin "8") (pinfunction "8_8") (pintype "passive"))
      (node (ref "JP101") (pin "9") (pinfunction "9_9") (pintype "passive"))
    )
    (net (code "91") (name "B(CS)") (class "Default")
      (node (ref "IC107") (pin "17") (pinfunction "B2_17") (pintype "bidirectional"))
      (node (ref "J103") (pin "7") (pinfunction "7_7") (pintype "passive"))
      (node (ref "JP101") (pin "10") (pinfunction "10_10") (pintype "passive"))
    )
    (net (code "92") (name "BLUE1") (class "Default")
      (node (ref "IC106") (pin "16") (pinfunction "B3_16") (pintype "bidirectional"))
      (node (ref "JP101") (pin "3") (pinfunction "3_3") (pintype "passive"))
    )
    (net (code "93") (name "BLUE2") (class "Default")
      (node (ref "IC106") (pin "13") (pinfunction "B6_13") (pintype "bidirectional"))
      (node (ref "JP101") (pin "7") (pinfunction "7_7") (pintype "passive"))
    )
    (net (code "94") (name "BUZZER") (class "Default")
      (node (ref "IC107") (pin "11") (pinfunction "B8_11") (pintype "bidirectional"))
      (node (ref "R108") (pin "2") (pinfunction "2_2") (pintype "passive"))
    )
    (net (code "95") (name "C(LOCK)") (class "Default")
      (node (ref "IC107") (pin "16") (pinfunction "B3_16") (pintype "bidirectional"))
      (node (ref "J103") (pin "10") (pinfunction "10_10") (pintype "passive"))
      (node (ref "JP101") (pin "11") (pinfunction "11_11") (pintype "passive"))
    )
    (net (code "96") (name "CLOCK") (class "Default")
      (node (ref "IC106") (pin "12") (pinfunction "B7_12") (pintype "bidirectional"))
      (node (ref "JP101") (pin "13") (pinfunction "13_13") (pintype "passive"))
    )
    (net (code "97") (name "D(ATA)") (class "Default")
      (node (ref "IC107") (pin "15") (pinfunction "B4_15") (pintype "bidirectional"))
      (node (ref "J103") (pin "9") (pinfunction "9_9") (pintype "passive"))
      (node (ref "JP101") (pin "12") (pinfunction "12_12") (pintype "passive"))
    )
    (net (code "98") (name "E") (class "Default")
      (node (ref "IC107") (pin "14") (pinfunction "B5_14") (pintype "bidirectional"))
      (node (ref "JP101") (pin "8") (pinfunction "8_8") (pintype "passive"))
    )
    (net (code "99") (name "GND") (class "Default")
      (node (ref "B101") (pin "-") (pinfunction "-_-") (pintype "passive"))
      (node (ref "C101") (pin "1") (pinfunction "1_1") (pintype "passive"))
      (node (ref "C102") (pin "2") (pinfunction "2_2") (pintype "passive"))
      (node (ref "C103") (pin "1") (pinfunction "1_1") (pintype "passive"))
      (node (ref "C104") (pin "2") (pinfunction "-_2") (pintype "passive"))
      (node (ref "C105") (pin "2") (pinfunction "2_2") (pintype "passive"))
      (node (ref "C106") (pin "1") (pinfunction "1_1") (pintype "passive"))
      (node (ref "C107") (pin "2") (pinfunction "2_2") (pintype "passive"))
      (node (ref "C108") (pin "2") (pinfunction "-_2") (pintype "passive"))
      (node (ref "C109") (pin "2") (pinfunction "2_2") (pintype "passive"))
      (node (ref "C110") (pin "1") (pinfunction "1_1") (pintype "passive"))
      (node (ref "C111") (pin "1") (pinfunction "1_1") (pintype "passive"))
      (node (ref "C112") (pin "1") (pinfunction "1_1") (pintype "passive"))
      (node (ref "C113") (pin "2") (pinfunction "2_2") (pintype "passive"))
      (node (ref "C114") (pin "2") (pinfunction "2_2") (pintype "passive"))
      (node (ref "C115") (pin "2") (pinfunction "2_2") (pintype "passive"))
      (node (ref "C116") (pin "1") (pinfunction "1_1") (pintype "passive"))
      (node (ref "C117") (pin "1") (pinfunction "1_1") (pintype "passive"))
      (node (ref "C201") (pin "1") (pinfunction "1_1") (pintype "passive"))
      (node (ref "C202") (pin "1") (pinfunction "1_1") (pintype "passive"))
      (node (ref "C203") (pin "1") (pinfunction "1_1") (pintype "passive"))
      (node (ref "C204") (pin "1") (pinfunction "1_1") (pintype "passive"))
      (node (ref "C205") (pin "1") (pinfunction "1_1") (pintype "passive"))
      (node (ref "C206") (pin "1") (pinfunction "1_1") (pintype "passive"))
      (node (ref "C207") (pin "1") (pinfunction "1_1") (pintype "passive"))
      (node (ref "C208") (pin "1") (pinfunction "1_1") (pintype "passive"))
      (node (ref "C209") (pin "1") (pinfunction "1_1") (pintype "passive"))
      (node (ref "C301") (pin "2") (pinfunction "-_2") (pintype "passive"))
      (node (ref "C302") (pin "2") (pinfunction "2_2") (pintype "passive"))
      (node (ref "C303") (pin "1") (pinfunction "1_1") (pintype "passive"))
      (node (ref "C304") (pin "2") (pinfunction "2_2") (pintype "passive"))
      (node (ref "C305") (pin "2") (pinfunction "-_2") (pintype "passive"))
      (node (ref "C306") (pin "1") (pinfunction "1_1") (pintype "passive"))
      (node (ref "C307") (pin "1") (pinfunction "1_1") (pintype "passive"))
      (node (ref "G101") (pin "-") (pinfunction "-_-") (pintype "passive"))
      (node (ref "G102") (pin "P\"-\"") (pinfunction "-_P\"-\"") (pintype "passive"))
      (node (ref "HA101") (pin "C") (pinfunction "C_C") (pintype "passive"))
      (node (ref "IC101") (pin "IN-") (pinfunction "IN-_IN-") (pintype "bidirectional"))
      (node (ref "IC101") (pin "OUT-") (pinfunction "OUT-_OUT-") (pintype "bidirectional"))
      (node (ref "IC102") (pin "10") (pinfunction "GND_10") (pintype "bidirectional"))
      (node (ref "IC102") (pin "11") (pinfunction "GND_11") (pintype "bidirectional"))
      (node (ref "IC102") (pin "12") (pinfunction "GND_12") (pintype "bidirectional"))
      (node (ref "IC102") (pin "13") (pinfunction "GND_13") (pintype "bidirectional"))
      (node (ref "IC102") (pin "5") (pinfunction "GND_5") (pintype "bidirectional"))
      (node (ref "IC102") (pin "6") (pinfunction "GND_6") (pintype "bidirectional"))
      (node (ref "IC102") (pin "7") (pinfunction "GND_7") (pintype "bidirectional"))
      (node (ref "IC102") (pin "8") (pinfunction "GND_8") (pintype "bidirectional"))
      (node (ref "IC102") (pin "9") (pinfunction "GND_9") (pintype "bidirectional"))
      (node (ref "IC103") (pin "1") (pinfunction "GND_1") (pintype "input"))
      (node (ref "IC104") (pin "2") (pinfunction "ADDR_2") (pintype "input"))
      (node (ref "IC104") (pin "3") (pinfunction "GND_3") (pintype "power_in"))
      (node (ref "IC105") (pin "1") (pinfunction "GND_1") (pintype "bidirectional"))
      (node (ref "IC105") (pin "7") (pinfunction "GND_7") (pintype "bidirectional"))
      (node (ref "IC106") (pin "10") (pinfunction "GND_10") (pintype "power_in"))
      (node (ref "IC106") (pin "19") (pinfunction "G_19") (pintype "input"))
      (node (ref "IC107") (pin "10") (pinfunction "GND_10") (pintype "power_in"))
      (node (ref "IC107") (pin "19") (pinfunction "G_19") (pintype "input"))
      (node (ref "IC201") (pin "GND1") (pinfunction "GND_GND1") (pintype "power_in"))
      (node (ref "IC201") (pin "GND2") (pinfunction "GND_GND2") (pintype "power_in"))
      (node (ref "IC201") (pin "GND3") (pinfunction "GND_GND3") (pintype "power_in"))
      (node (ref "IC201") (pin "PAD0") (pinfunction "GND_PAD0") (pintype "power_in"))
      (node (ref "IC201") (pin "PAD1") (pinfunction "GND_PAD1") (pintype "power_in"))
      (node (ref "IC201") (pin "PAD2") (pinfunction "GND_PAD2") (pintype "power_in"))
      (node (ref "IC201") (pin "PAD3") (pinfunction "GND_PAD3") (pintype "power_in"))
      (node (ref "IC201") (pin "PAD4") (pinfunction "GND_PAD4") (pintype "power_in"))
      (node (ref "IC201") (pin "PAD5") (pinfunction "GND_PAD5") (pintype "power_in"))
      (node (ref "IC201") (pin "PAD6") (pinfunction "GND_PAD6") (pintype "power_in"))
      (node (ref "IC201") (pin "PAD7") (pinfunction "GND_PAD7") (pintype "power_in"))
      (node (ref "IC201") (pin "PAD8") (pinfunction "GND_PAD8") (pintype "power_in"))
      (node (ref "IC202") (pin "GND") (pinfunction "GND_GND") (pintype "bidirectional"))
      (node (ref "IC203") (pin "GND") (pinfunction "GND_GND") (pintype "power_in"))
      (node (ref "IC204") (pin "GND") (pinfunction "GND_GND") (pintype "bidirectional"))
      (node (ref "IC301") (pin "1") (pinfunction "GND_1") (pintype "input"))
      (node (ref "IC302") (pin "1") (pinfunction "GND_1") (pintype "bidirectional"))
      (node (ref "IC302") (pin "7") (pinfunction "GND_7") (pintype "bidirectional"))
      (node (ref "J101") (pin "1") (pinfunction "1_1") (pintype "passive"))
      (node (ref "J102") (pin "4") (pinfunction "4_4") (pintype "passive"))
      (node (ref "J103") (pin "3") (pinfunction "3_3") (pintype "passive"))
      (node (ref "J103") (pin "4") (pinfunction "4_4") (pintype "passive"))
      (node (ref "J103") (pin "5") (pinfunction "5_5") (pintype "passive"))
      (node (ref "J103") (pin "6") (pinfunction "6_6") (pintype "passive"))
      (node (ref "J104") (pin "4") (pinfunction "4_4") (pintype "bidirectional"))
      (node (ref "J105") (pin "4") (pinfunction "4_4") (pintype "bidirectional"))
      (node (ref "J201") (pin "GND") (pinfunction "GND_GND") (pintype "power_in"))
      (node (ref "J201") (pin "SH@1") (pinfunction "SHIELD_SH@1") (pintype "bidirectional"))
      (node (ref "J201") (pin "SH@2") (pinfunction "SHIELD_SH@2") (pintype "bidirectional"))
      (node (ref "J201") (pin "SH@3") (pinfunction "SHIELD_SH@3") (pintype "bidirectional"))
      (node (ref "J201") (pin "SH@4") (pinfunction "SHIELD_SH@4") (pintype "bidirectional"))
      (node (ref "J201") (pin "SH@5") (pinfunction "SHIELD_SH@5") (pintype "bidirectional"))
      (node (ref "J201") (pin "SH@6") (pinfunction "SHIELD_SH@6") (pintype "bidirectional"))
      (node (ref "J202") (pin "4") (pinfunction "4_4") (pintype "passive"))
      (node (ref "J203") (pin "4") (pinfunction "4_4") (pintype "passive"))
      (node (ref "J204") (pin "4") (pinfunction "4_4") (pintype "passive"))
      (node (ref "J205") (pin "4") (pinfunction "4_4") (pintype "passive"))
      (node (ref "J206") (pin "GND") (pinfunction "GND_GND") (pintype "power_in"))
      (node (ref "J206") (pin "SH@1") (pinfunction "SHIELD_SH@1") (pintype "bidirectional"))
      (node (ref "J206") (pin "SH@2") (pinfunction "SHIELD_SH@2") (pintype "bidirectional"))
      (node (ref "J206") (pin "SH@3") (pinfunction "SHIELD_SH@3") (pintype "bidirectional"))
      (node (ref "J206") (pin "SH@4") (pinfunction "SHIELD_SH@4") (pintype "bidirectional"))
      (node (ref "J206") (pin "SH@5") (pinfunction "SHIELD_SH@5") (pintype "bidirectional"))
      (node (ref "J206") (pin "SH@6") (pinfunction "SHIELD_SH@6") (pintype "bidirectional"))
      (node (ref "J207") (pin "3") (pinfunction "3_3") (pintype "passive"))
      (node (ref "J208") (pin "3") (pinfunction "3_3") (pintype "passive"))
      (node (ref "J209") (pin "3") (pinfunction "3_3") (pintype "passive"))
      (node (ref "J301") (pin "2") (pinfunction "2_2") (pintype "passive"))
      (node (ref "JP101") (pin "16") (pinfunction "16_16") (pintype "passive"))
      (node (ref "JP101") (pin "4") (pinfunction "4_4") (pintype "passive"))
      (node (ref "LED102") (pin "C") (pinfunction "C_C") (pintype "passive"))
      (node (ref "LED103") (pin "C") (pinfunction "C_C") (pintype "passive"))
      (node (ref "R102") (pin "1") (pinfunction "1_1") (pintype "passive"))
      (node (ref "R103") (pin "1") (pinfunction "P$1_1") (pintype "bidirectional"))
      (node (ref "R202") (pin "2") (pinfunction "2_2") (pintype "passive"))
      (node (ref "R204") (pin "2") (pinfunction "2_2") (pintype "passive"))
      (node (ref "R206") (pin "1") (pinfunction "1_1") (pintype "passive"))
      (node (ref "R209") (pin "1") (pinfunction "1_1") (pintype "passive"))
      (node (ref "SW101") (pin "A") (pinfunction "A_A") (pintype "passive"))
      (node (ref "SW101") (pin "SH0") (pinfunction "SH_SH0") (pintype "power_in"))
      (node (ref "SW102") (pin "A") (pinfunction "A_A") (pintype "passive"))
      (node (ref "SW102") (pin "SH0") (pinfunction "SH_SH0") (pintype "power_in"))
      (node (ref "U101") (pin "GND") (pinfunction "GND_GND") (pintype "power_in"))
      (node (ref "U301") (pin "GND") (pinfunction "GND_GND") (pintype "power_in"))
      (node (ref "X101") (pin "1") (pinfunction "S_1") (pintype "passive"))
      (node (ref "X102") (pin "4") (pinfunction "S_4") (pintype "passive"))
      (node (ref "X103") (pin "3") (pinfunction "S_3") (pintype "passive"))
      (node (ref "X301") (pin "1") (pinfunction "S_1") (pintype "passive"))
      (node (ref "X302") (pin "4") (pinfunction "S_4") (pintype "passive"))
      (node (ref "X303") (pin "3") (pinfunction "S_3") (pintype "passive"))
    )
    (net (code "100") (name "GREEN1") (class "Default")
      (node (ref "IC106") (pin "17") (pinfunction "B2_17") (pintype "bidirectional"))
      (node (ref "JP101") (pin "2") (pinfunction "2_2") (pintype "passive"))
    )
    (net (code "101") (name "GREEN2") (class "Default")
      (node (ref "IC106") (pin "14") (pinfunction "B5_14") (pintype "bidirectional"))
      (node (ref "JP101") (pin "6") (pinfunction "6_6") (pintype "passive"))
    )
    (net (code "102") (name "I2C_SCL") (class "Default")
      (node (ref "IC102") (pin "16") (pinfunction "SCL_16") (pintype "bidirectional"))
      (node (ref "IC104") (pin "6") (pinfunction "SCL_6") (pintype "bidirectional"))
      (node (ref "IC105") (pin "4") (pinfunction "SCK/SCL_4") (pintype "bidirectional"))
      (node (ref "J102") (pin "9") (pinfunction "9_9") (pintype "passive"))
      (node (ref "J104") (pin "1") (pinfunction "1_1") (pintype "bidirectional"))
      (node (ref "J105") (pin "1") (pinfunction "1_1") (pintype "bidirectional"))
      (node (ref "R113") (pin "2") (pinfunction "2_2") (pintype "passive"))
      (node (ref "U101") (pin "SCK") (pinfunction "SCK_SCK") (pintype "input"))
      (node (ref "X103") (pin "4") (pinfunction "S_4") (pintype "passive"))
    )
    (net (code "103") (name "I2C_SCL_S") (class "Default")
      (node (ref "IC302") (pin "4") (pinfunction "SCK/SCL_4") (pintype "bidirectional"))
      (node (ref "J301") (pin "7") (pinfunction "7_7") (pintype "passive"))
      (node (ref "R302") (pin "2") (pinfunction "2_2") (pintype "passive"))
      (node (ref "U301") (pin "SCK") (pinfunction "SCK_SCK") (pintype "input"))
      (node (ref "X303") (pin "4") (pinfunction "S_4") (pintype "passive"))
    )
    (net (code "104") (name "I2C_SDA") (class "Default")
      (node (ref "IC102") (pin "15") (pinfunction "SDA_15") (pintype "bidirectional"))
      (node (ref "IC104") (pin "4") (pinfunction "SDA_4") (pintype "bidirectional"))
      (node (ref "IC105") (pin "3") (pinfunction "SDI/SDA_3") (pintype "bidirectional"))
      (node (ref "J102") (pin "10") (pinfunction "10_10") (pintype "passive"))
      (node (ref "J104") (pin "2") (pinfunction "2_2") (pintype "bidirectional"))
      (node (ref "J105") (pin "2") (pinfunction "2_2") (pintype "bidirectional"))
      (node (ref "R114") (pin "2") (pinfunction "2_2") (pintype "passive"))
      (node (ref "U101") (pin "DATA") (pinfunction "DATA_DATA") (pintype "bidirectional"))
      (node (ref "X103") (pin "2") (pinfunction "S_2") (pintype "passive"))
    )
    (net (code "105") (name "I2C_SDA_S") (class "Default")
      (node (ref "IC302") (pin "3") (pinfunction "SDI/SDA_3") (pintype "bidirectional"))
      (node (ref "J301") (pin "8") (pinfunction "8_8") (pintype "passive"))
      (node (ref "R303") (pin "2") (pinfunction "2_2") (pintype "passive"))
      (node (ref "U301") (pin "DATA") (pinfunction "DATA_DATA") (pintype "bidirectional"))
      (node (ref "X303") (pin "2") (pinfunction "S_2") (pintype "passive"))
    )
    (net (code "106") (name "IN_A") (class "Default")
      (node (ref "IC107") (pin "2") (pinfunction "A1_2") (pintype "bidirectional"))
      (node (ref "J102") (pin "14") (pinfunction "14_14") (pintype "passive"))
    )
    (net (code "107") (name "IN_B") (class "Default")
      (node (ref "IC107") (pin "3") (pinfunction "A2_3") (pintype "bidirectional"))
      (node (ref "J102") (pin "13") (pinfunction "13_13") (pintype "passive"))
    )
    (net (code "108") (name "IN_BLUE1") (class "Default")
      (node (ref "IC106") (pin "4") (pinfunction "A3_4") (pintype "bidirectional"))
      (node (ref "J102") (pin "22") (pinfunction "22_22") (pintype "passive"))
    )
    (net (code "109") (name "IN_BLUE2") (class "Default")
      (node (ref "IC106") (pin "7") (pinfunction "A6_7") (pintype "bidirectional"))
      (node (ref "J102") (pin "23") (pinfunction "23_23") (pintype "passive"))
    )
    (net (code "110") (name "IN_BUZZER") (class "Default")
      (node (ref "IC107") (pin "9") (pinfunction "A8_9") (pintype "bidirectional"))
      (node (ref "J102") (pin "11") (pinfunction "11_11") (pintype "passive"))
    )
    (net (code "111") (name "IN_C") (class "Default")
      (node (ref "IC107") (pin "4") (pinfunction "A3_4") (pintype "bidirectional"))
      (node (ref "J102") (pin "16") (pinfunction "16_16") (pintype "passive"))
    )
    (net (code "112") (name "IN_CLOCK") (class "Default")
      (node (ref "IC106") (pin "8") (pinfunction "A7_8") (pintype "bidirectional"))
      (node (ref "J102") (pin "26") (pinfunction "26_26") (pintype "passive"))
    )
    (net (code "113") (name "IN_D") (class "Default")
      (node (ref "IC107") (pin "5") (pinfunction "A4_5") (pintype "bidirectional"))
      (node (ref "J102") (pin "15") (pinfunction "15_15") (pintype "passive"))
    )
    (net (code "114") (name "IN_DHT") (class "Default")
      (node (ref "J102") (pin "7") (pinfunction "7_7") (pintype "passive"))
      (node (ref "R106") (pin "2") (pinfunction "2_2") (pintype "passive"))
      (node (ref "X102") (pin "2") (pinfunction "S_2") (pintype "passive"))
    )
    (net (code "115") (name "IN_DHT_S") (class "Default")
      (node (ref "J301") (pin "5") (pinfunction "5_5") (pintype "passive"))
      (node (ref "R301") (pin "2") (pinfunction "2_2") (pintype "passive"))
      (node (ref "X302") (pin "2") (pinfunction "S_2") (pintype "passive"))
    )
    (net (code "116") (name "IN_E") (class "Default")
      (node (ref "IC107") (pin "6") (pinfunction "A5_6") (pintype "bidirectional"))
      (node (ref "J102") (pin "18") (pinfunction "18_18") (pintype "passive"))
    )
    (net (code "117") (name "IN_GREEN1") (class "Default")
      (node (ref "IC106") (pin "3") (pinfunction "A2_3") (pintype "bidirectional"))
      (node (ref "J102") (pin "19") (pinfunction "19_19") (pintype "passive"))
    )
    (net (code "118") (name "IN_GREEN2") (class "Default")
      (node (ref "IC106") (pin "6") (pinfunction "A5_6") (pintype "bidirectional"))
      (node (ref "J102") (pin "24") (pinfunction "24_24") (pintype "passive"))
    )
    (net (code "119") (name "IN_LATCH") (class "Default")
      (node (ref "IC106") (pin "9") (pinfunction "A8_9") (pintype "bidirectional"))
      (node (ref "J102") (pin "25") (pinfunction "25_25") (pintype "passive"))
    )
    (net (code "120") (name "IN_LED") (class "Default")
      (node (ref "IC107") (pin "8") (pinfunction "A7_8") (pintype "bidirectional"))
      (node (ref "J102") (pin "12") (pinfunction "12_12") (pintype "passive"))
    )
    (net (code "121") (name "IN_OE") (class "Default")
      (node (ref "IC107") (pin "7") (pinfunction "A6_7") (pintype "bidirectional"))
      (node (ref "J102") (pin "17") (pinfunction "17_17") (pintype "passive"))
    )
    (net (code "122") (name "IN_RED1") (class "Default")
      (node (ref "IC106") (pin "2") (pinfunction "A1_2") (pintype "bidirectional"))
      (node (ref "J102") (pin "20") (pinfunction "20_20") (pintype "passive"))
    )
    (net (code "123") (name "IN_RED2") (class "Default")
      (node (ref "IC106") (pin "5") (pinfunction "A4_5") (pintype "bidirectional"))
      (node (ref "J102") (pin "21") (pinfunction "21_21") (pintype "passive"))
    )
    (net (code "124") (name "LATCH") (class "Default")
      (node (ref "IC106") (pin "11") (pinfunction "B8_11") (pintype "bidirectional"))
      (node (ref "JP101") (pin "14") (pinfunction "14_14") (pintype "passive"))
    )
    (net (code "125") (name "LED") (class "Default")
      (node (ref "IC107") (pin "12") (pinfunction "B7_12") (pintype "bidirectional"))
      (node (ref "R110") (pin "2") (pinfunction "2_2") (pintype "passive"))
    )
    (net (code "126") (name "Net-(D201-PadA)") (class "Default")
      (node (ref "D201") (pin "A") (pinfunction "A_A") (pintype "passive"))
      (node (ref "J203") (pin "2") (pinfunction "2_2") (pintype "passive"))
    )
    (net (code "127") (name "Net-(D202-PadA)") (class "Default")
      (node (ref "D202") (pin "A") (pinfunction "A_A") (pintype "passive"))
      (node (ref "J204") (pin "2") (pinfunction "2_2") (pintype "passive"))
    )
    (net (code "128") (name "Net-(D203-PadA)") (class "Default")
      (node (ref "D203") (pin "A") (pinfunction "A_A") (pintype "passive"))
      (node (ref "J202") (pin "2") (pinfunction "2_2") (pintype "passive"))
    )
    (net (code "129") (name "Net-(G102-+)") (class "Default")
      (node (ref "B101") (pin "+") (pinfunction "+_+") (pintype "passive"))
      (node (ref "D102") (pin "A") (pinfunction "A_A") (pintype "passive"))
      (node (ref "G101") (pin "+") (pinfunction "+_+") (pintype "passive"))
      (node (ref "G102") (pin "P1\"+\"") (pinfunction "+_P1\"+\"") (pintype "passive"))
    )
    (net (code "130") (name "Net-(HA101-PadA)") (class "Default")
      (node (ref "HA101") (pin "A") (pinfunction "A_A") (pintype "passive"))
      (node (ref "R108") (pin "1") (pinfunction "1_1") (pintype "passive"))
    )
    (net (code "131") (name "Net-(IC102-32KHZ)") (class "Default")
      (node (ref "IC102") (pin "1") (pinfunction "32KHZ_1") (pintype "output"))
      (node (ref "R104") (pin "1") (pinfunction "1_1") (pintype "passive"))
    )
    (net (code "132") (name "Net-(IC102-VBAT)") (class "Default")
      (node (ref "D101") (pin "C") (pinfunction "C_C") (pintype "passive"))
      (node (ref "D102") (pin "C") (pinfunction "C_C") (pintype "passive"))
      (node (ref "IC102") (pin "14") (pinfunction "VBAT_14") (pintype "bidirectional"))
    )
    (net (code "133") (name "Net-(IC104-DVI)") (class "Default")
      (node (ref "C109") (pin "1") (pinfunction "1_1") (pintype "passive"))
      (node (ref "IC104") (pin "5") (pinfunction "DVI_5") (pintype "bidirectional"))
      (node (ref "R107") (pin "2") (pinfunction "2_2") (pintype "passive"))
    )
    (net (code "134") (name "Net-(IC202-PadCH_PD)") (class "Default")
      (node (ref "IC202") (pin "CH_PD") (pinfunction "CH_PD_CH_PD") (pintype "bidirectional"))
      (node (ref "R201") (pin "1") (pinfunction "1_1") (pintype "passive"))
    )
    (net (code "135") (name "Net-(IC204-PadADC)") (class "Default")
      (node (ref "IC204") (pin "ADC") (pinfunction "ADC_ADC") (pintype "bidirectional"))
      (node (ref "R204") (pin "1") (pinfunction "1_1") (pintype "passive"))
    )
    (net (code "136") (name "Net-(IC204-PadCH_PD)") (class "Default")
      (node (ref "IC204") (pin "CH_PD") (pinfunction "CH_PD_CH_PD") (pintype "bidirectional"))
      (node (ref "R205") (pin "1") (pinfunction "1_1") (pintype "passive"))
    )
    (net (code "137") (name "Net-(IC204-PadGPIO0)") (class "Default")
      (node (ref "IC204") (pin "GPIO0") (pinfunction "GPIO0_GPIO0") (pintype "bidirectional"))
      (node (ref "R208") (pin "1") (pinfunction "1_1") (pintype "passive"))
    )
    (net (code "138") (name "Net-(IC204-PadGPIO2)") (class "Default")
      (node (ref "IC204") (pin "GPIO2") (pinfunction "GPIO2_GPIO2") (pintype "bidirectional"))
      (node (ref "R207") (pin "1") (pinfunction "1_1") (pintype "passive"))
    )
    (net (code "139") (name "Net-(J207-Pad11)") (class "Default")
      (node (ref "J207") (pin "11") (pinfunction "11_11") (pintype "passive"))
      (node (ref "SJ201") (pin "3") (pinfunction "3_3") (pintype "passive"))
    )
    (net (code "140") (name "Net-(J207-Pad13)") (class "Default")
      (node (ref "J207") (pin "13") (pinfunction "13_13") (pintype "passive"))
      (node (ref "SJ201") (pin "2") (pinfunction "2_2") (pintype "passive"))
    )
    (net (code "141") (name "Net-(J209-Pad8)") (class "Default")
      (node (ref "J209") (pin "8") (pinfunction "8_8") (pintype "passive"))
      (node (ref "SJ203") (pin "1") (pinfunction "1_1") (pintype "passive"))
    )
    (net (code "142") (name "Net-(J209-Pad11)") (class "Default")
      (node (ref "J209") (pin "11") (pinfunction "11_11") (pintype "passive"))
      (node (ref "SJ202") (pin "3") (pinfunction "3_3") (pintype "passive"))
    )
    (net (code "143") (name "Net-(J209-Pad13)") (class "Default")
      (node (ref "J209") (pin "13") (pinfunction "13_13") (pintype "passive"))
      (node (ref "SJ202") (pin "2") (pinfunction "2_2") (pintype "passive"))
    )
    (net (code "144") (name "Net-(LED101-PadC)") (class "Default")
      (node (ref "LED101") (pin "C") (pinfunction "C_C") (pintype "passive"))
      (node (ref "R105") (pin "2") (pinfunction "2_2") (pintype "passive"))
    )
    (net (code "145") (name "Net-(LED102-PadA)") (class "Default")
      (node (ref "LED102") (pin "A") (pinfunction "A_A") (pintype "passive"))
      (node (ref "R110") (pin "1") (pinfunction "1_1") (pintype "passive"))
    )
    (net (code "146") (name "Net-(LED103-PadA)") (class "Default")
      (node (ref "LED103") (pin "A") (pinfunction "A_A") (pintype "passive"))
      (node (ref "R111") (pin "1") (pinfunction "1_1") (pintype "passive"))
    )
    (net (code "147") (name "Net-(LED201-PadC)") (class "Default")
      (node (ref "LED201") (pin "C") (pinfunction "C_C") (pintype "passive"))
      (node (ref "R207") (pin "2") (pinfunction "2_2") (pintype "passive"))
    )
    (net (code "148") (name "Net-(LED202-PadC)") (class "Default")
      (node (ref "LED202") (pin "C") (pinfunction "C_C") (pintype "passive"))
      (node (ref "R208") (pin "2") (pinfunction "2_2") (pintype "passive"))
    )
    (net (code "149") (name "Net-(R113-Pad1)") (class "Default")
      (node (ref "R113") (pin "1") (pinfunction "1_1") (pintype "passive"))
      (node (ref "R114") (pin "1") (pinfunction "1_1") (pintype "passive"))
      (node (ref "SJ102") (pin "2") (pinfunction "2_2") (pintype "passive"))
    )
    (net (code "150") (name "Net-(R302-Pad1)") (class "Default")
      (node (ref "R302") (pin "1") (pinfunction "1_1") (pintype "passive"))
      (node (ref "R303") (pin "1") (pinfunction "1_1") (pintype "passive"))
      (node (ref "SJ301") (pin "2") (pinfunction "2_2") (pintype "passive"))
    )
    (net (code "151") (name "OE") (class "Default")
      (node (ref "IC107") (pin "13") (pinfunction "B6_13") (pintype "bidirectional"))
      (node (ref "JP101") (pin "15") (pinfunction "15_15") (pintype "passive"))
    )
    (net (code "152") (name "PHOTO_RES") (class "Default")
      (node (ref "J102") (pin "8") (pinfunction "8_8") (pintype "passive"))
      (node (ref "R101") (pin "1") (pinfunction "1_1") (pintype "passive"))
      (node (ref "R102") (pin "2") (pinfunction "2_2") (pintype "passive"))
      (node (ref "R103") (pin "2") (pinfunction "P$2_2") (pintype "bidirectional"))
    )
    (net (code "153") (name "PRG_BTN") (class "Default")
      (node (ref "J102") (pin "1") (pinfunction "1_1") (pintype "passive"))
      (node (ref "R109") (pin "1") (pinfunction "1_1") (pintype "passive"))
      (node (ref "SW101") (pin "B") (pinfunction "B_B") (pintype "passive"))
    )
    (net (code "154") (name "RED1") (class "Default")
      (node (ref "IC106") (pin "18") (pinfunction "B1_18") (pintype "bidirectional"))
      (node (ref "JP101") (pin "1") (pinfunction "1_1") (pintype "passive"))
    )
    (net (code "155") (name "RED2") (class "Default")
      (node (ref "IC106") (pin "15") (pinfunction "B4_15") (pintype "bidirectional"))
      (node (ref "JP101") (pin "5") (pinfunction "5_5") (pintype "passive"))
    )
    (net (code "156") (name "RST_BTN") (class "Default")
      (node (ref "C112") (pin "2") (pinfunction "2_2") (pintype "passive"))
      (node (ref "J102") (pin "2") (pinfunction "2_2") (pintype "passive"))
      (node (ref "R112") (pin "2") (pinfunction "2_2") (pintype "passive"))
      (node (ref "SW102") (pin "B") (pinfunction "B_B") (pintype "passive"))
    )
    (net (code "157") (name "SQW") (class "Default")
      (node (ref "IC102") (pin "3") (pinfunction "INT_3") (pintype "bidirectional"))
      (node (ref "J102") (pin "6") (pinfunction "6_6") (pintype "passive"))
      (node (ref "R105") (pin "1") (pinfunction "1_1") (pintype "passive"))
    )
    (net (code "158") (name "VCC") (class "Default")
      (node (ref "C114") (pin "1") (pinfunction "1_1") (pintype "passive"))
      (node (ref "C115") (pin "1") (pinfunction "1_1") (pintype "passive"))
      (node (ref "IC106") (pin "1") (pinfunction "DIR_1") (pintype "input"))
      (node (ref "IC106") (pin "20") (pinfunction "VCC_20") (pintype "power_in"))
      (node (ref "IC107") (pin "1") (pinfunction "DIR_1") (pintype "input"))
      (node (ref "IC107") (pin "20") (pinfunction "VCC_20") (pintype "power_in"))
      (node (ref "SJ103") (pin "1") (pinfunction "1_1") (pintype "passive"))
      (node (ref "SJ104") (pin "3") (pinfunction "3_3") (pintype "passive"))
    )
    (net (code "159") (name "V_SPI") (class "Default")
      (node (ref "C113") (pin "1") (pinfunction "1_1") (pintype "passive"))
      (node (ref "J103") (pin "1") (pinfunction "1_1") (pintype "passive"))
      (node (ref "J103") (pin "2") (pinfunction "2_2") (pintype "passive"))
      (node (ref "SJ104") (pin "1") (pinfunction "1_1") (pintype "passive"))
    )
    (net (code "160") (name "unconnected-(IC102-RST-Pad4)") (class "Default")
      (node (ref "IC102") (pin "4") (pinfunction "RST_4") (pintype "bidirectional"))
    )
    (net (code "161") (name "unconnected-(IC105-SDO{slash}ADR-Pad5)") (class "Default")
      (node (ref "IC105") (pin "5") (pinfunction "SDO/ADR_5") (pintype "bidirectional"))
    )
    (net (code "162") (name "unconnected-(IC105-~{CS}-Pad2)") (class "Default")
      (node (ref "IC105") (pin "2") (pinfunction "~{CS}_2") (pintype "bidirectional"))
    )
    (net (code "163") (name "unconnected-(IC302-SDO{slash}ADR-Pad5)") (class "Default")
      (node (ref "IC302") (pin "5") (pinfunction "SDO/ADR_5") (pintype "bidirectional"))
    )
    (net (code "164") (name "unconnected-(IC302-~{CS}-Pad2)") (class "Default")
      (node (ref "IC302") (pin "2") (pinfunction "~{CS}_2") (pintype "bidirectional"))
    )
    (net (code "165") (name "unconnected-(J101-Pad2)") (class "Default")
      (node (ref "J101") (pin "2") (pinfunction "2_2") (pintype "passive"))
    )
    (net (code "166") (name "unconnected-(J201-PadID)") (class "Default")
      (node (ref "J201") (pin "ID") (pinfunction "ID_ID") (pintype "bidirectional"))
    )
    (net (code "167") (name "unconnected-(J206-PadID)") (class "Default")
      (node (ref "J206") (pin "ID") (pinfunction "ID_ID") (pintype "bidirectional"))
    )
    (net (code "168") (name "unconnected-(J301-Pad4)") (class "Default")
      (node (ref "J301") (pin "4") (pinfunction "4_4") (pintype "passive"))
    )
    (net (code "169") (name "unconnected-(J301-Pad6)") (class "Default")
      (node (ref "J301") (pin "6") (pinfunction "6_6") (pintype "passive"))
    )
    (net (code "170") (name "unconnected-(X102C-S-Pad3)") (class "Default")
      (node (ref "X102") (pin "3") (pinfunction "S_3") (pintype "passive"))
    )
    (net (code "171") (name "unconnected-(X302C-S-Pad3)") (class "Default")
      (node (ref "X302") (pin "3") (pinfunction "S_3") (pintype "passive"))
    )
  )
)
